# octanis_eps_v2.net
KiCad netlist of a schematic drawn in EAGLE
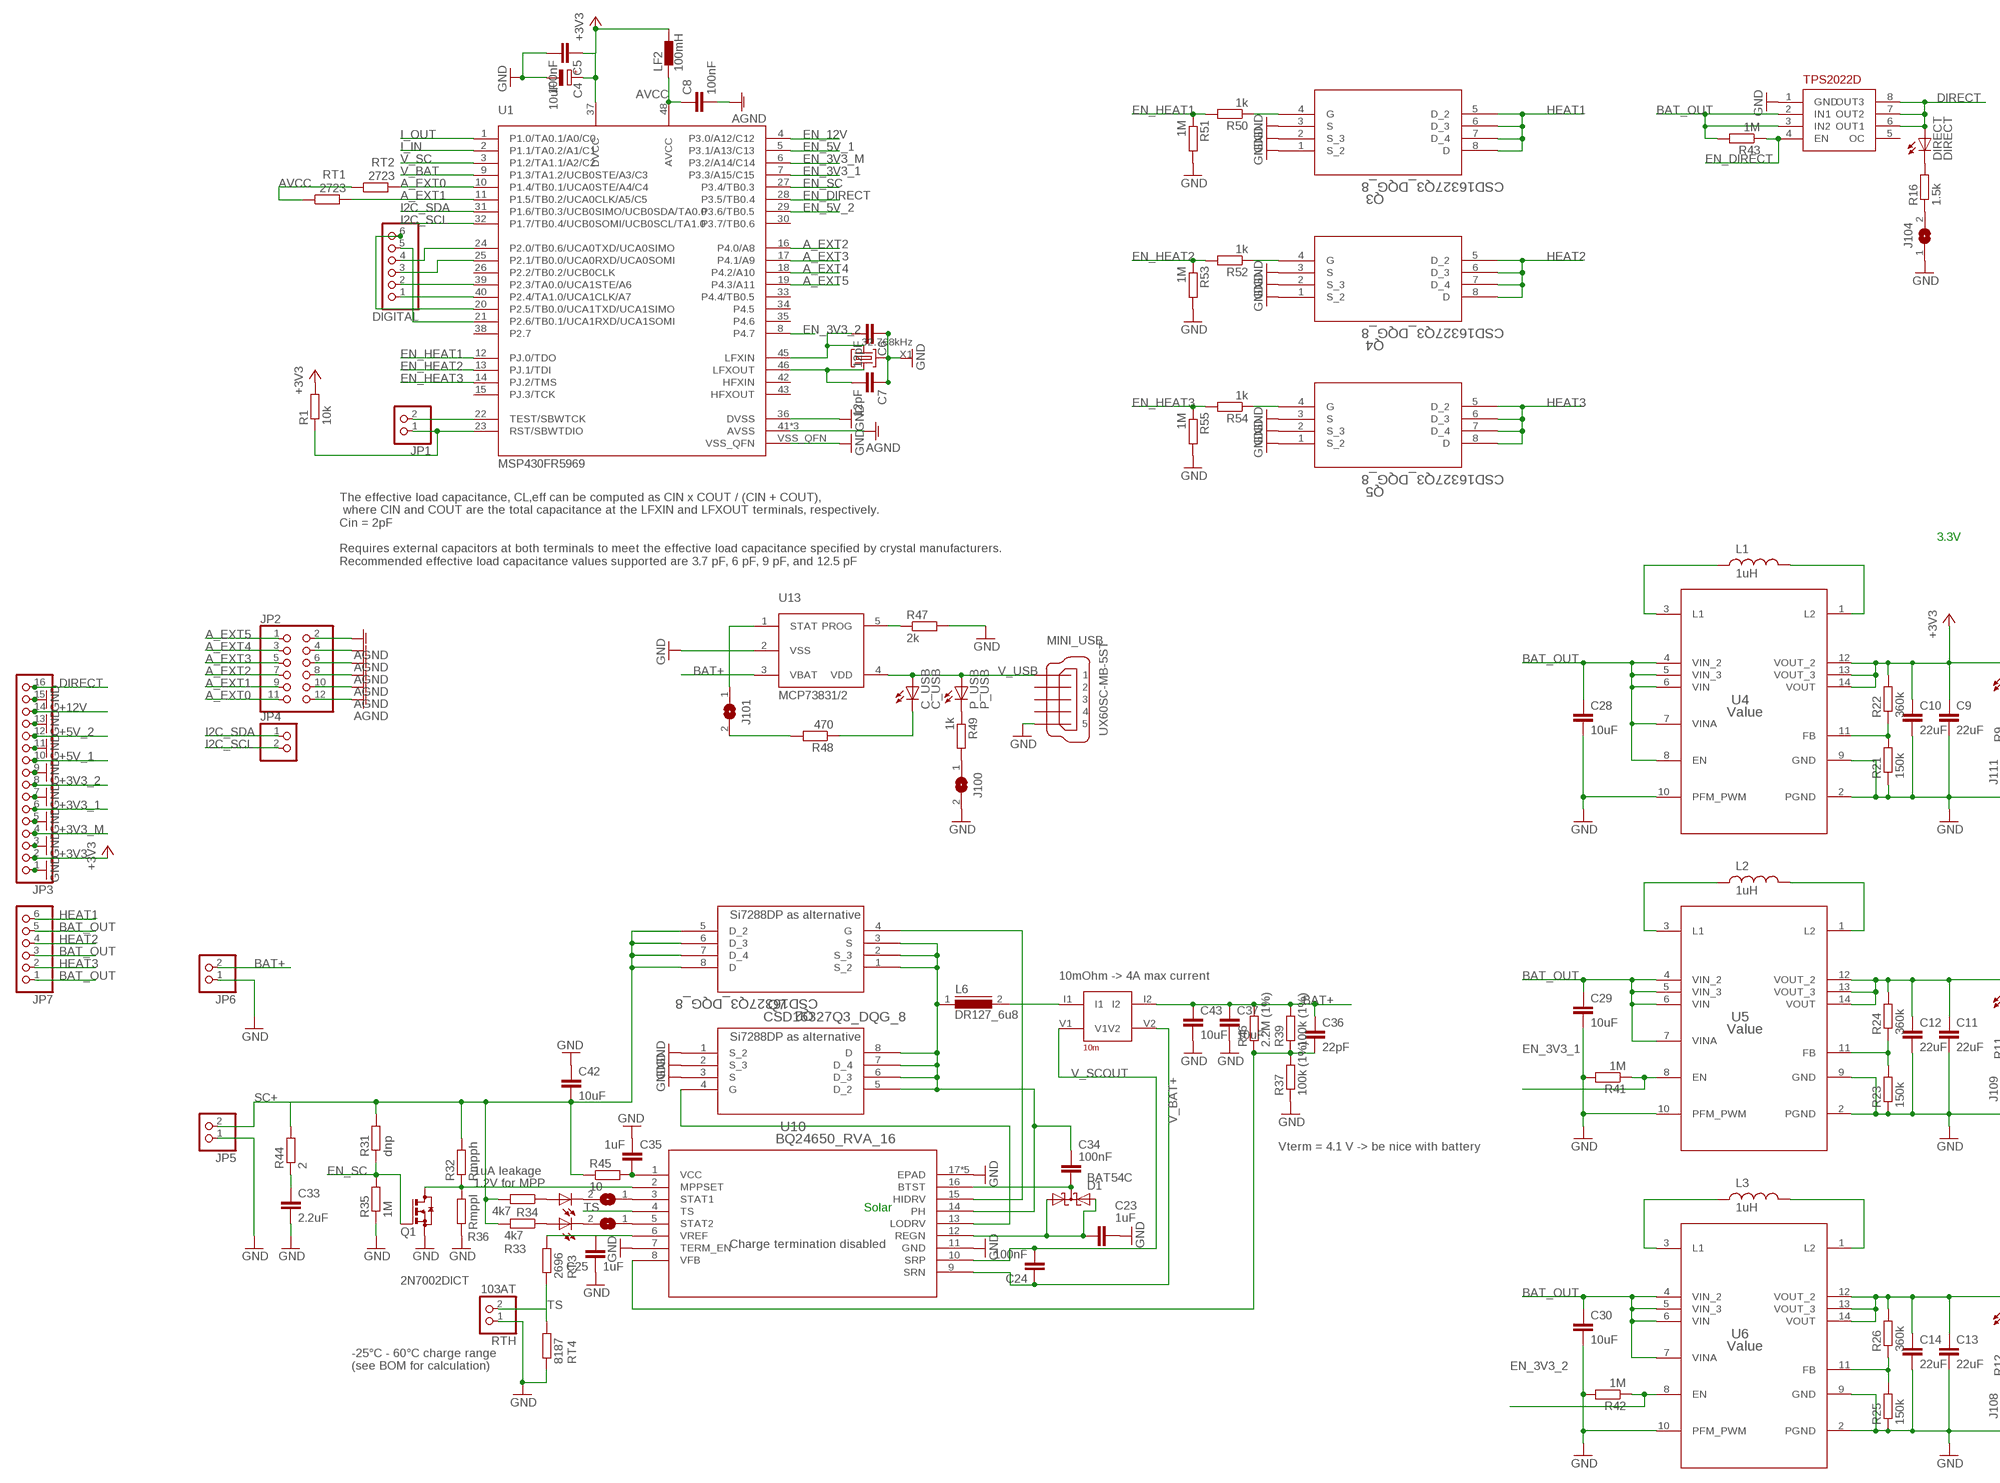
[diagram p0: schematic, sheet 1, part 1 of 2]
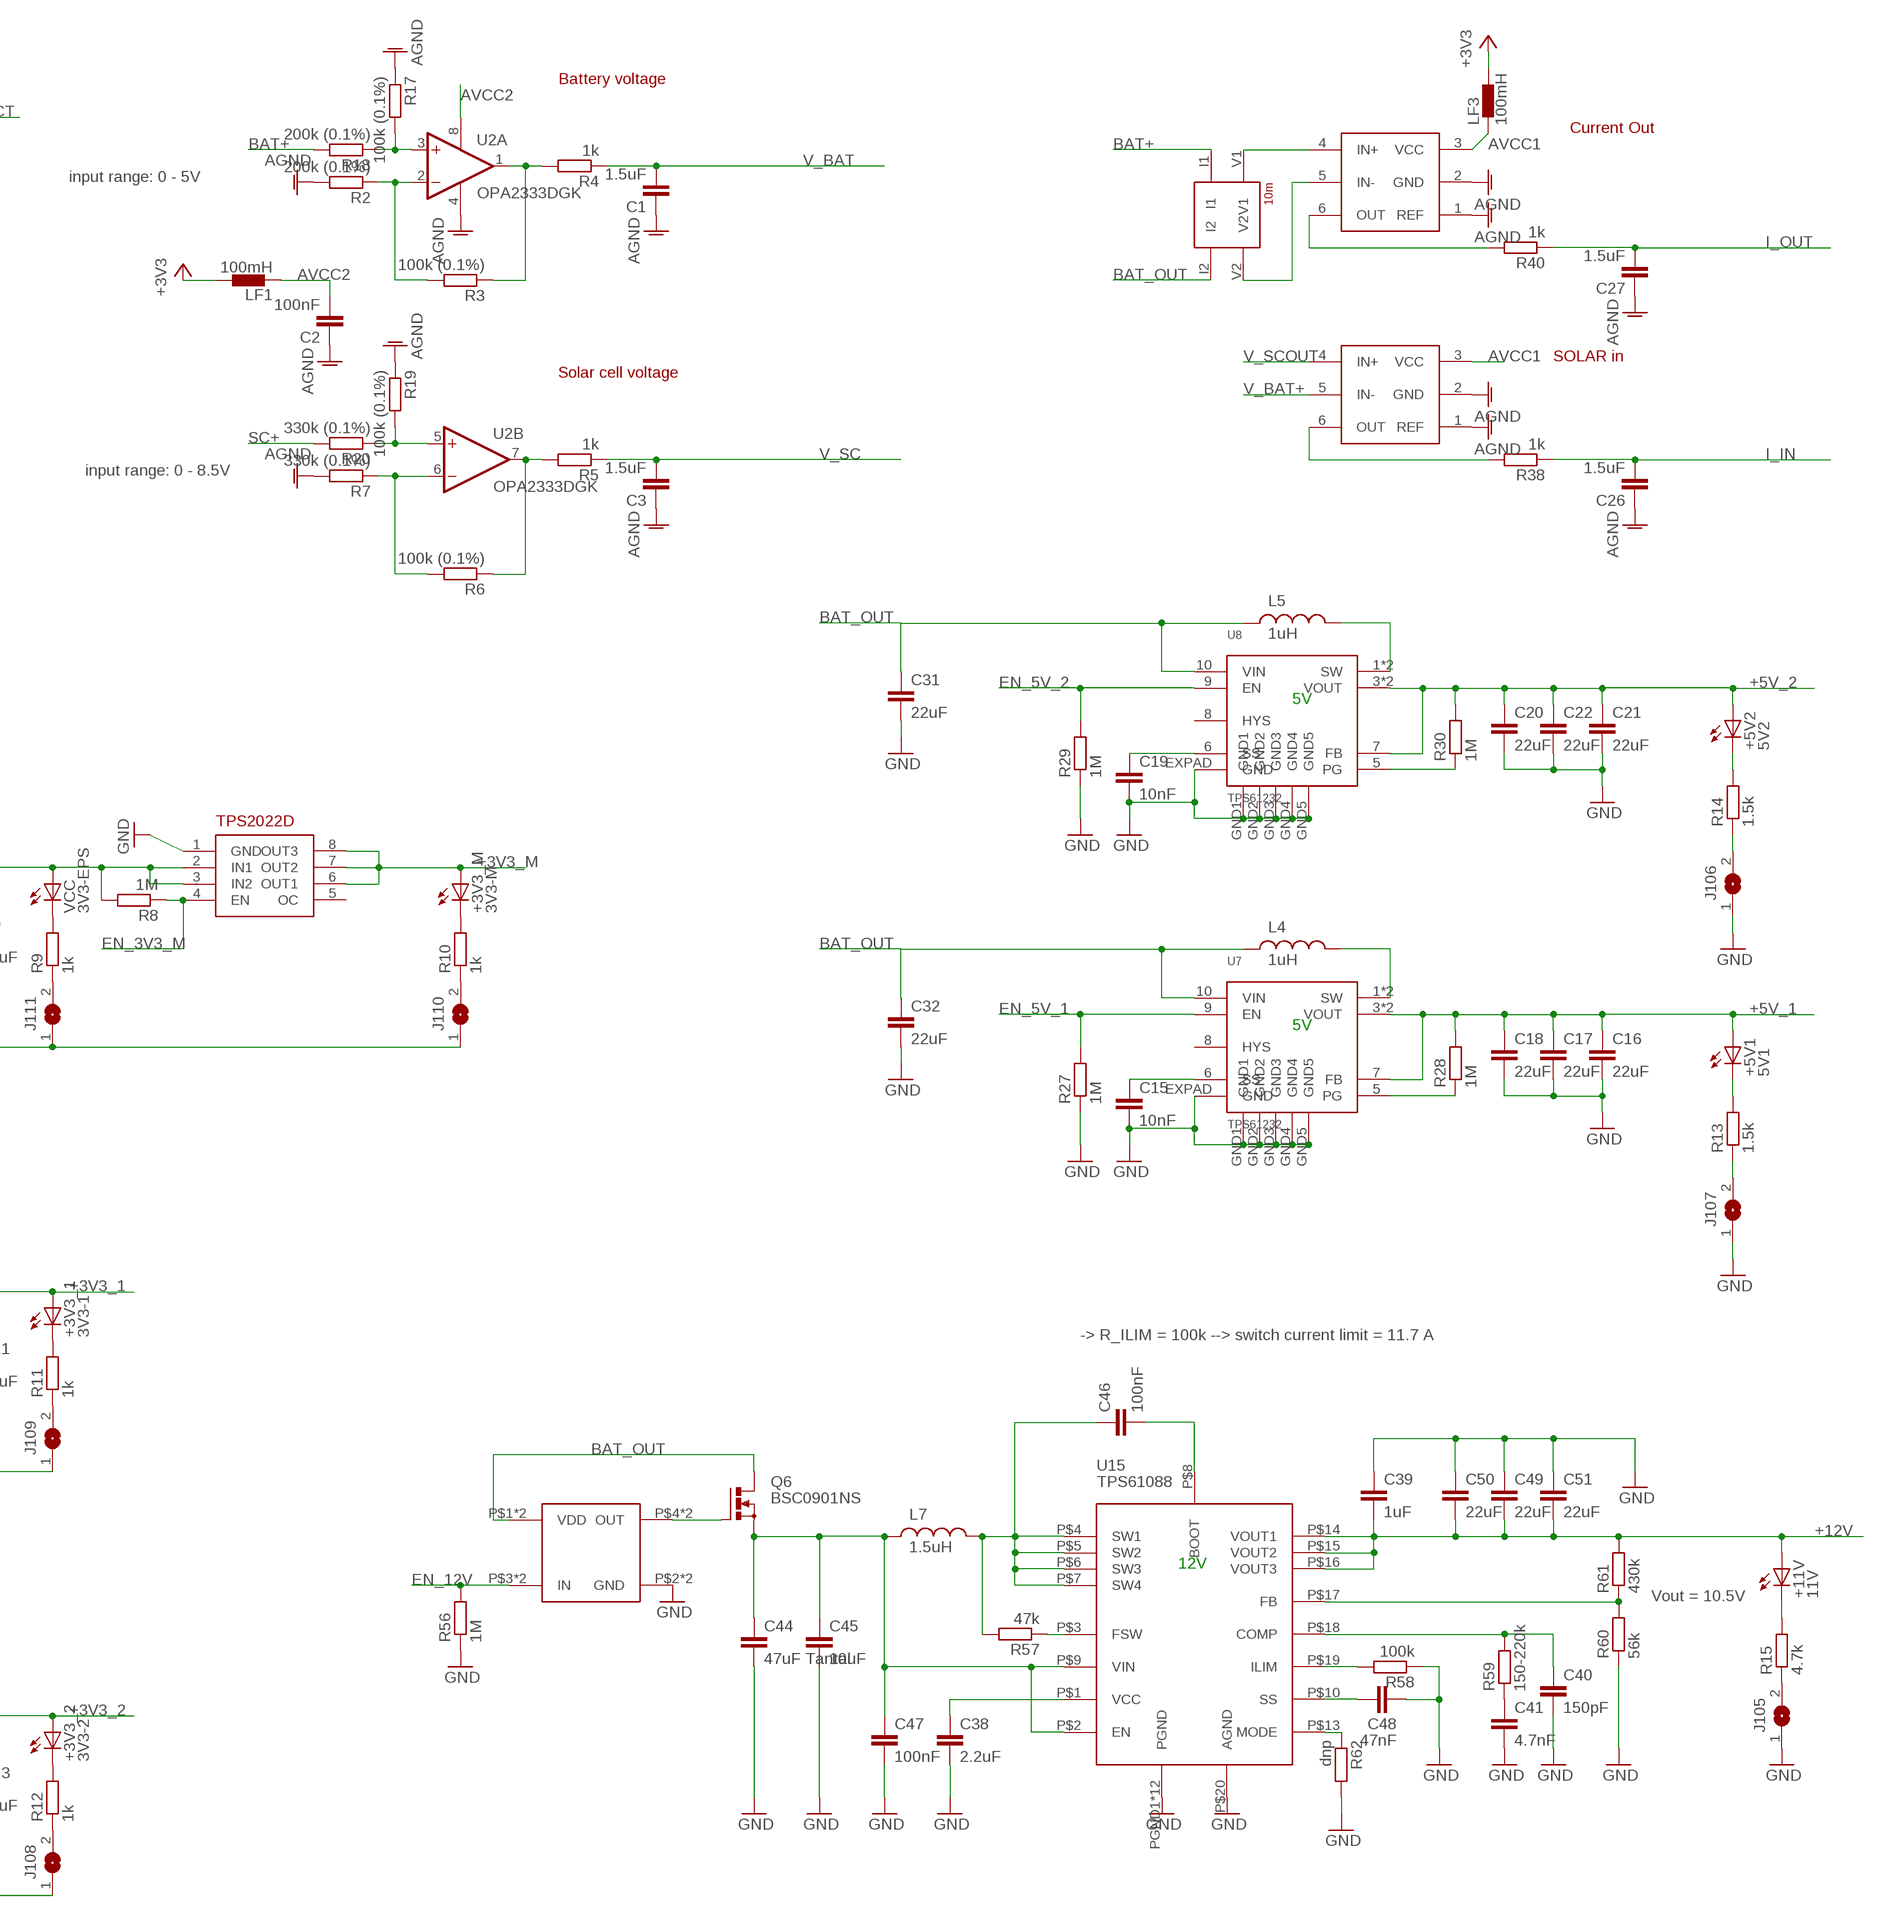
[diagram p1: schematic, sheet 1, part 2 of 2]

(export (version "E")
  (design (tool "Eeschema 10.0.6"))
  (components
    (comp (ref "+3V3_1")
      (value "3V3-1")
      (footprint "eagle-import:CHIPLED_0603")
      (libsource (lib "eagle-import") (part "LEDCHIPLED_0603"))
    )
    (comp (ref "+3V3_2")
      (value "3V3-2")
      (footprint "eagle-import:CHIPLED_0603")
      (libsource (lib "eagle-import") (part "LEDCHIPLED_0603"))
    )
    (comp (ref "+3V3_M")
      (value "3V3-M")
      (footprint "eagle-import:CHIPLED_0603")
      (libsource (lib "eagle-import") (part "LEDCHIPLED_0603"))
    )
    (comp (ref "+5V1")
      (value "5V1")
      (footprint "eagle-import:CHIPLED_0603")
      (libsource (lib "eagle-import") (part "LEDCHIPLED_0603"))
    )
    (comp (ref "+5V2")
      (value "5V2")
      (footprint "eagle-import:CHIPLED_0603")
      (libsource (lib "eagle-import") (part "LEDCHIPLED_0603"))
    )
    (comp (ref "+11V")
      (value "11V")
      (footprint "eagle-import:CHIPLED_0603")
      (libsource (lib "eagle-import") (part "LEDCHIPLED_0603"))
    )
    (comp (ref "C1")
      (value "1.5uF")
      (footprint "eagle-import:C0603")
      (libsource (lib "eagle-import") (part "C-EUC0603"))
    )
    (comp (ref "C2")
      (value "100nF")
      (footprint "eagle-import:C0603")
      (libsource (lib "eagle-import") (part "C-EUC0603"))
    )
    (comp (ref "C3")
      (value "1.5uF")
      (footprint "eagle-import:C0603")
      (libsource (lib "eagle-import") (part "C-EUC0603"))
    )
    (comp (ref "C4")
      (value "10uF")
      (footprint "eagle-import:A_3216-18R")
      (libsource (lib "eagle-import") (part "CPOL-EUA/3216-18R"))
    )
    (comp (ref "C5")
      (value "100nF")
      (footprint "eagle-import:C0603")
      (libsource (lib "eagle-import") (part "C-EUC0603"))
    )
    (comp (ref "C6")
      (value "12pF")
      (footprint "eagle-import:C0603")
      (libsource (lib "eagle-import") (part "C-EUC0603"))
    )
    (comp (ref "C7")
      (value "12pF")
      (footprint "eagle-import:C0603")
      (libsource (lib "eagle-import") (part "C-EUC0603"))
    )
    (comp (ref "C8")
      (value "100nF")
      (footprint "eagle-import:C0603")
      (libsource (lib "eagle-import") (part "C-EUC0603"))
    )
    (comp (ref "C9")
      (value "22uF")
      (footprint "eagle-import:C0805")
      (libsource (lib "eagle-import") (part "resistor_C-EUC0805"))
    )
    (comp (ref "C10")
      (value "22uF")
      (footprint "eagle-import:C0805")
      (libsource (lib "eagle-import") (part "resistor_C-EUC0805"))
    )
    (comp (ref "C11")
      (value "22uF")
      (footprint "eagle-import:C0805")
      (libsource (lib "eagle-import") (part "resistor_C-EUC0805"))
    )
    (comp (ref "C12")
      (value "22uF")
      (footprint "eagle-import:C0805")
      (libsource (lib "eagle-import") (part "resistor_C-EUC0805"))
    )
    (comp (ref "C13")
      (value "22uF")
      (footprint "eagle-import:C0805")
      (libsource (lib "eagle-import") (part "resistor_C-EUC0805"))
    )
    (comp (ref "C14")
      (value "22uF")
      (footprint "eagle-import:C0805")
      (libsource (lib "eagle-import") (part "resistor_C-EUC0805"))
    )
    (comp (ref "C15")
      (value "10nF")
      (footprint "eagle-import:C0603")
      (libsource (lib "eagle-import") (part "C-EUC0603"))
    )
    (comp (ref "C16")
      (value "22uF")
      (footprint "eagle-import:C0805")
      (libsource (lib "eagle-import") (part "resistor_C-EUC0805"))
    )
    (comp (ref "C17")
      (value "22uF")
      (footprint "eagle-import:C0805")
      (libsource (lib "eagle-import") (part "resistor_C-EUC0805"))
    )
    (comp (ref "C18")
      (value "22uF")
      (footprint "eagle-import:C0805")
      (libsource (lib "eagle-import") (part "resistor_C-EUC0805"))
    )
    (comp (ref "C19")
      (value "10nF")
      (footprint "eagle-import:C0603")
      (libsource (lib "eagle-import") (part "C-EUC0603"))
    )
    (comp (ref "C20")
      (value "22uF")
      (footprint "eagle-import:C0805")
      (libsource (lib "eagle-import") (part "resistor_C-EUC0805"))
    )
    (comp (ref "C21")
      (value "22uF")
      (footprint "eagle-import:C0805")
      (libsource (lib "eagle-import") (part "resistor_C-EUC0805"))
    )
    (comp (ref "C22")
      (value "22uF")
      (footprint "eagle-import:C0805")
      (libsource (lib "eagle-import") (part "resistor_C-EUC0805"))
    )
    (comp (ref "C23")
      (value "1uF")
      (footprint "eagle-import:C0603")
      (libsource (lib "eagle-import") (part "C-EUC0603"))
    )
    (comp (ref "C24")
      (value "100nF")
      (footprint "eagle-import:C0603")
      (libsource (lib "eagle-import") (part "C-EUC0603"))
    )
    (comp (ref "C25")
      (value "1uF")
      (footprint "eagle-import:C0603")
      (libsource (lib "eagle-import") (part "C-EUC0603"))
    )
    (comp (ref "C26")
      (value "1.5uF")
      (footprint "eagle-import:C0603")
      (libsource (lib "eagle-import") (part "C-EUC0603"))
    )
    (comp (ref "C27")
      (value "1.5uF")
      (footprint "eagle-import:C0603")
      (libsource (lib "eagle-import") (part "C-EUC0603"))
    )
    (comp (ref "C28")
      (value "10uF")
      (footprint "eagle-import:C0805")
      (libsource (lib "eagle-import") (part "resistor_C-EUC0805"))
    )
    (comp (ref "C29")
      (value "10uF")
      (footprint "eagle-import:C0805")
      (libsource (lib "eagle-import") (part "resistor_C-EUC0805"))
    )
    (comp (ref "C30")
      (value "10uF")
      (footprint "eagle-import:C0805")
      (libsource (lib "eagle-import") (part "resistor_C-EUC0805"))
    )
    (comp (ref "C31")
      (value "22uF")
      (footprint "eagle-import:C0805")
      (libsource (lib "eagle-import") (part "resistor_C-EUC0805"))
    )
    (comp (ref "C32")
      (value "22uF")
      (footprint "eagle-import:C0805")
      (libsource (lib "eagle-import") (part "resistor_C-EUC0805"))
    )
    (comp (ref "C33")
      (value "2.2uF")
      (footprint "eagle-import:C0603")
      (libsource (lib "eagle-import") (part "C-EUC0603"))
    )
    (comp (ref "C34")
      (value "100nF")
      (footprint "eagle-import:C0603")
      (libsource (lib "eagle-import") (part "C-EUC0603"))
    )
    (comp (ref "C35")
      (value "1uF")
      (footprint "eagle-import:C0603")
      (libsource (lib "eagle-import") (part "C-EUC0603"))
    )
    (comp (ref "C36")
      (value "22pF")
      (footprint "eagle-import:C0603")
      (libsource (lib "eagle-import") (part "C-EUC0603"))
    )
    (comp (ref "C37")
      (value "10uF")
      (footprint "eagle-import:C0805")
      (libsource (lib "eagle-import") (part "resistor_C-EUC0805"))
    )
    (comp (ref "C38")
      (value "2.2uF")
      (footprint "eagle-import:C0603")
      (libsource (lib "eagle-import") (part "C-EUC0603"))
    )
    (comp (ref "C39")
      (value "1uF")
      (footprint "eagle-import:C0603")
      (libsource (lib "eagle-import") (part "C-EUC0603"))
    )
    (comp (ref "C40")
      (value "150pF")
      (footprint "eagle-import:C0603")
      (libsource (lib "eagle-import") (part "C-EUC0603"))
    )
    (comp (ref "C41")
      (value "4.7nF")
      (footprint "eagle-import:C0603")
      (libsource (lib "eagle-import") (part "C-EUC0603"))
    )
    (comp (ref "C42")
      (value "10uF")
      (footprint "eagle-import:C0805")
      (libsource (lib "eagle-import") (part "resistor_C-EUC0805"))
    )
    (comp (ref "C43")
      (value "10uF")
      (footprint "eagle-import:C0805")
      (libsource (lib "eagle-import") (part "resistor_C-EUC0805"))
    )
    (comp (ref "C44")
      (value "47uF Tantal")
      (footprint "eagle-import:C1210")
      (libsource (lib "eagle-import") (part "C-EUC1210"))
    )
    (comp (ref "C45")
      (value "10uF")
      (footprint "eagle-import:C0805")
      (libsource (lib "eagle-import") (part "resistor_C-EUC0805"))
    )
    (comp (ref "C46")
      (value "100nF")
      (footprint "eagle-import:C0603")
      (libsource (lib "eagle-import") (part "C-EUC0603"))
    )
    (comp (ref "C47")
      (value "100nF")
      (footprint "eagle-import:C0603")
      (libsource (lib "eagle-import") (part "C-EUC0603"))
    )
    (comp (ref "C48")
      (value "47nF")
      (footprint "eagle-import:C0603")
      (libsource (lib "eagle-import") (part "C-EUC0603"))
    )
    (comp (ref "C49")
      (value "22uF")
      (footprint "eagle-import:C0805")
      (libsource (lib "eagle-import") (part "resistor_C-EUC0805"))
    )
    (comp (ref "C50")
      (value "22uF")
      (footprint "eagle-import:C0805")
      (libsource (lib "eagle-import") (part "resistor_C-EUC0805"))
    )
    (comp (ref "C51")
      (value "22uF")
      (footprint "eagle-import:C0805")
      (libsource (lib "eagle-import") (part "resistor_C-EUC0805"))
    )
    (comp (ref "C_USB")
      (value "C_USB")
      (footprint "eagle-import:CHIPLED_0603")
      (libsource (lib "eagle-import") (part "LEDCHIPLED_0603"))
    )
    (comp (ref "D1")
      (value "BAT54C")
      (footprint "eagle-import:SOT23")
      (libsource (lib "eagle-import") (part "BAT54C"))
    )
    (comp (ref "DIGITAL")
      (value "PINHD-1X6B")
      (footprint "eagle-import:1X06-BIG")
      (libsource (lib "eagle-import") (part "PINHD-1X6B"))
    )
    (comp (ref "DIRECT")
      (value "DIRECT")
      (footprint "eagle-import:CHIPLED_0603")
      (libsource (lib "eagle-import") (part "LEDCHIPLED_0603"))
    )
    (comp (ref "J100")
      (value "SJ")
      (footprint "eagle-import:SJ")
      (libsource (lib "eagle-import") (part "SJ"))
    )
    (comp (ref "J101")
      (value "SJ")
      (footprint "eagle-import:SJ")
      (libsource (lib "eagle-import") (part "SJ"))
    )
    (comp (ref "J102")
      (value "SJ")
      (footprint "eagle-import:SJ")
      (libsource (lib "eagle-import") (part "SJ"))
    )
    (comp (ref "J103")
      (value "SJ")
      (footprint "eagle-import:SJ")
      (libsource (lib "eagle-import") (part "SJ"))
    )
    (comp (ref "J104")
      (value "SJ")
      (footprint "eagle-import:SJ")
      (libsource (lib "eagle-import") (part "SJ"))
    )
    (comp (ref "J105")
      (value "SJ")
      (footprint "eagle-import:SJ")
      (libsource (lib "eagle-import") (part "SJ"))
    )
    (comp (ref "J106")
      (value "SJ")
      (footprint "eagle-import:SJ")
      (libsource (lib "eagle-import") (part "SJ"))
    )
    (comp (ref "J107")
      (value "SJ")
      (footprint "eagle-import:SJ")
      (libsource (lib "eagle-import") (part "SJ"))
    )
    (comp (ref "J108")
      (value "SJ")
      (footprint "eagle-import:SJ")
      (libsource (lib "eagle-import") (part "SJ"))
    )
    (comp (ref "J109")
      (value "SJ")
      (footprint "eagle-import:SJ")
      (libsource (lib "eagle-import") (part "SJ"))
    )
    (comp (ref "J110")
      (value "SJ")
      (footprint "eagle-import:SJ")
      (libsource (lib "eagle-import") (part "SJ"))
    )
    (comp (ref "J111")
      (value "SJ")
      (footprint "eagle-import:SJ")
      (libsource (lib "eagle-import") (part "SJ"))
    )
    (comp (ref "JP1")
      (value "PINHD-1X2")
      (footprint "eagle-import:1X02")
      (libsource (lib "eagle-import") (part "PINHD-1X2"))
    )
    (comp (ref "JP2")
      (value "PINHD-2X6")
      (footprint "eagle-import:2X06")
      (libsource (lib "eagle-import") (part "PINHD-2X6"))
    )
    (comp (ref "JP3")
      (value "PINHD-1X16")
      (footprint "eagle-import:1X16")
      (libsource (lib "eagle-import") (part "PINHD-1X16"))
    )
    (comp (ref "JP4")
      (value "PINHD-1X2")
      (footprint "eagle-import:1X02")
      (libsource (lib "eagle-import") (part "PINHD-1X2"))
    )
    (comp (ref "JP5")
      (value "PINHD-1X2")
      (footprint "eagle-import:1X02")
      (libsource (lib "eagle-import") (part "PINHD-1X2"))
    )
    (comp (ref "JP6")
      (value "PINHD-1X2")
      (footprint "eagle-import:1X02")
      (libsource (lib "eagle-import") (part "PINHD-1X2"))
    )
    (comp (ref "JP7")
      (value "PINHD-1X6")
      (footprint "eagle-import:1X06")
      (libsource (lib "eagle-import") (part "PINHD-1X6"))
    )
    (comp (ref "L1")
      (value "1uH")
      (footprint "eagle-import:XFL4020")
      (libsource (lib "eagle-import") (part "XFL4020"))
    )
    (comp (ref "L2")
      (value "1uH")
      (footprint "eagle-import:XFL4020")
      (libsource (lib "eagle-import") (part "XFL4020"))
    )
    (comp (ref "L3")
      (value "1uH")
      (footprint "eagle-import:XFL4020")
      (libsource (lib "eagle-import") (part "XFL4020"))
    )
    (comp (ref "L4")
      (value "1uH")
      (footprint "eagle-import:XFL4020")
      (libsource (lib "eagle-import") (part "XFL4020"))
    )
    (comp (ref "L5")
      (value "1uH")
      (footprint "eagle-import:XFL4020")
      (libsource (lib "eagle-import") (part "XFL4020"))
    )
    (comp (ref "L6")
      (value "DR127_6u8")
      (footprint "eagle-import:DR127")
      (libsource (lib "eagle-import") (part "DR127"))
    )
    (comp (ref "L7")
      (value "1.5uH")
      (footprint "eagle-import:XFL4020")
      (libsource (lib "eagle-import") (part "XFL4020"))
    )
    (comp (ref "LF1")
      (value "100mH")
      (footprint "eagle-import:0402")
      (libsource (lib "eagle-import") (part "BLM15HD601SN1"))
    )
    (comp (ref "LF2")
      (value "100mH")
      (footprint "eagle-import:0402")
      (libsource (lib "eagle-import") (part "BLM15HD601SN1"))
    )
    (comp (ref "LF3")
      (value "100mH")
      (footprint "eagle-import:0402")
      (libsource (lib "eagle-import") (part "BLM15HD601SN1"))
    )
    (comp (ref "MINI_USB")
      (value "UX60SC-MB-5ST")
      (footprint "eagle-import:UX60SC-MB-5ST")
      (libsource (lib "eagle-import") (part "UX60SC-MB-5ST"))
    )
    (comp (ref "P_USB")
      (value "P_USB")
      (footprint "eagle-import:CHIPLED_0603")
      (libsource (lib "eagle-import") (part "LEDCHIPLED_0603"))
    )
    (comp (ref "Q1")
      (value "BSS123")
      (footprint "eagle-import:SOT23")
      (libsource (lib "eagle-import") (part "BSS123"))
    )
    (comp (ref "Q2")
      (value "CSD16327Q3_DQG_8")
      (footprint "eagle-import:DQG8")
      (fields
        (field (name "GENERIC_PART_NUMBER") "CSD16327Q3")
        (field (name "MANUFACTURER") "Texas Instruments")
      )
      (libsource (lib "eagle-import") (part "CSD16327Q3_DQG_8"))
    )
    (comp (ref "Q3")
      (value "CSD16327Q3_DQG_8")
      (footprint "eagle-import:DQG8")
      (fields
        (field (name "GENERIC_PART_NUMBER") "CSD16327Q3")
        (field (name "MANUFACTURER") "Texas Instruments")
      )
      (libsource (lib "eagle-import") (part "CSD16327Q3_DQG_8"))
    )
    (comp (ref "Q4")
      (value "CSD16327Q3_DQG_8")
      (footprint "eagle-import:DQG8")
      (fields
        (field (name "GENERIC_PART_NUMBER") "CSD16327Q3")
        (field (name "MANUFACTURER") "Texas Instruments")
      )
      (libsource (lib "eagle-import") (part "CSD16327Q3_DQG_8"))
    )
    (comp (ref "Q5")
      (value "CSD16327Q3_DQG_8")
      (footprint "eagle-import:DQG8")
      (fields
        (field (name "GENERIC_PART_NUMBER") "CSD16327Q3")
        (field (name "MANUFACTURER") "Texas Instruments")
      )
      (libsource (lib "eagle-import") (part "CSD16327Q3_DQG_8"))
    )
    (comp (ref "Q6")
      (value "BSC0901NS")
      (footprint "eagle-import:PG-TDSON-8")
      (libsource (lib "eagle-import") (part "BSC340N08NS3G"))
    )
    (comp (ref "Q7")
      (value "CSD16327Q3_DQG_8")
      (footprint "eagle-import:DQG8")
      (fields
        (field (name "GENERIC_PART_NUMBER") "CSD16327Q3")
        (field (name "MANUFACTURER") "Texas Instruments")
      )
      (libsource (lib "eagle-import") (part "CSD16327Q3_DQG_8"))
    )
    (comp (ref "R1")
      (value "10k")
      (footprint "eagle-import:R0603")
      (libsource (lib "eagle-import") (part "R-EU_R0603"))
    )
    (comp (ref "R2")
      (value "200k (0.1%)")
      (footprint "eagle-import:R0603")
      (libsource (lib "eagle-import") (part "R-EU_R0603"))
    )
    (comp (ref "R3")
      (value "100k (0.1%)")
      (footprint "eagle-import:R0603")
      (libsource (lib "eagle-import") (part "R-EU_R0603"))
    )
    (comp (ref "R4")
      (value "1k")
      (footprint "eagle-import:R0603")
      (libsource (lib "eagle-import") (part "R-EU_R0603"))
    )
    (comp (ref "R5")
      (value "1k")
      (footprint "eagle-import:R0603")
      (libsource (lib "eagle-import") (part "R-EU_R0603"))
    )
    (comp (ref "R6")
      (value "100k (0.1%)")
      (footprint "eagle-import:R0603")
      (libsource (lib "eagle-import") (part "R-EU_R0603"))
    )
    (comp (ref "R7")
      (value "330k (0.1%)")
      (footprint "eagle-import:R0603")
      (libsource (lib "eagle-import") (part "R-EU_R0603"))
    )
    (comp (ref "R8")
      (value "1M")
      (footprint "eagle-import:R0603")
      (libsource (lib "eagle-import") (part "resistor_R-EU_R0603"))
    )
    (comp (ref "R9")
      (value "1k")
      (footprint "eagle-import:R0603")
      (libsource (lib "eagle-import") (part "R-EU_R0603"))
    )
    (comp (ref "R10")
      (value "1k")
      (footprint "eagle-import:R0603")
      (libsource (lib "eagle-import") (part "R-EU_R0603"))
    )
    (comp (ref "R11")
      (value "1k")
      (footprint "eagle-import:R0603")
      (libsource (lib "eagle-import") (part "R-EU_R0603"))
    )
    (comp (ref "R12")
      (value "1k")
      (footprint "eagle-import:R0603")
      (libsource (lib "eagle-import") (part "R-EU_R0603"))
    )
    (comp (ref "R13")
      (value "1.5k")
      (footprint "eagle-import:R0603")
      (libsource (lib "eagle-import") (part "R-EU_R0603"))
    )
    (comp (ref "R14")
      (value "1.5k")
      (footprint "eagle-import:R0603")
      (libsource (lib "eagle-import") (part "R-EU_R0603"))
    )
    (comp (ref "R15")
      (value "4.7k")
      (footprint "eagle-import:R0603")
      (libsource (lib "eagle-import") (part "R-EU_R0603"))
    )
    (comp (ref "R16")
      (value "1.5k")
      (footprint "eagle-import:R0603")
      (libsource (lib "eagle-import") (part "R-EU_R0603"))
    )
    (comp (ref "R17")
      (value "100k (0.1%)")
      (footprint "eagle-import:R0603")
      (libsource (lib "eagle-import") (part "R-EU_R0603"))
    )
    (comp (ref "R18")
      (value "200k (0.1%)")
      (footprint "eagle-import:R0603")
      (libsource (lib "eagle-import") (part "R-EU_R0603"))
    )
    (comp (ref "R19")
      (value "100k (0.1%)")
      (footprint "eagle-import:R0603")
      (libsource (lib "eagle-import") (part "R-EU_R0603"))
    )
    (comp (ref "R20")
      (value "330k (0.1%)")
      (footprint "eagle-import:R0603")
      (libsource (lib "eagle-import") (part "R-EU_R0603"))
    )
    (comp (ref "R21")
      (value "150k")
      (footprint "eagle-import:R0603")
      (libsource (lib "eagle-import") (part "R-EU_R0603"))
    )
    (comp (ref "R22")
      (value "360k")
      (footprint "eagle-import:R0603")
      (libsource (lib "eagle-import") (part "R-EU_R0603"))
    )
    (comp (ref "R23")
      (value "150k")
      (footprint "eagle-import:R0603")
      (libsource (lib "eagle-import") (part "R-EU_R0603"))
    )
    (comp (ref "R24")
      (value "360k")
      (footprint "eagle-import:R0603")
      (libsource (lib "eagle-import") (part "R-EU_R0603"))
    )
    (comp (ref "R25")
      (value "150k")
      (footprint "eagle-import:R0603")
      (libsource (lib "eagle-import") (part "R-EU_R0603"))
    )
    (comp (ref "R26")
      (value "360k")
      (footprint "eagle-import:R0603")
      (libsource (lib "eagle-import") (part "R-EU_R0603"))
    )
    (comp (ref "R27")
      (value "1M")
      (footprint "eagle-import:R0603")
      (libsource (lib "eagle-import") (part "R-EU_R0603"))
    )
    (comp (ref "R28")
      (value "1M")
      (footprint "eagle-import:R0603")
      (libsource (lib "eagle-import") (part "R-EU_R0603"))
    )
    (comp (ref "R29")
      (value "1M")
      (footprint "eagle-import:R0603")
      (libsource (lib "eagle-import") (part "R-EU_R0603"))
    )
    (comp (ref "R30")
      (value "1M")
      (footprint "eagle-import:R0603")
      (libsource (lib "eagle-import") (part "R-EU_R0603"))
    )
    (comp (ref "R31")
      (value "dnp")
      (footprint "eagle-import:R0603")
      (libsource (lib "eagle-import") (part "R-EU_R0603"))
    )
    (comp (ref "R32")
      (value "Rmpph")
      (footprint "eagle-import:R0603")
      (libsource (lib "eagle-import") (part "R-EU_R0603"))
    )
    (comp (ref "R33")
      (value "4k7")
      (footprint "eagle-import:R0603")
      (libsource (lib "eagle-import") (part "R-EU_R0603"))
    )
    (comp (ref "R34")
      (value "4k7")
      (footprint "eagle-import:R0603")
      (libsource (lib "eagle-import") (part "R-EU_R0603"))
    )
    (comp (ref "R35")
      (value "1M")
      (footprint "eagle-import:R0603")
      (libsource (lib "eagle-import") (part "R-EU_R0603"))
    )
    (comp (ref "R36")
      (value "Rmppl")
      (footprint "eagle-import:R0603")
      (libsource (lib "eagle-import") (part "R-EU_R0603"))
    )
    (comp (ref "R37")
      (value "100k (1%)")
      (footprint "eagle-import:R0603")
      (libsource (lib "eagle-import") (part "R-EU_R0603"))
    )
    (comp (ref "R38")
      (value "1k")
      (footprint "eagle-import:R0603")
      (libsource (lib "eagle-import") (part "R-EU_R0603"))
    )
    (comp (ref "R39")
      (value "100k (1%)")
      (footprint "eagle-import:R0603")
      (libsource (lib "eagle-import") (part "R-EU_R0603"))
    )
    (comp (ref "R40")
      (value "1k")
      (footprint "eagle-import:R0603")
      (libsource (lib "eagle-import") (part "R-EU_R0603"))
    )
    (comp (ref "R41")
      (value "1M")
      (footprint "eagle-import:R0603")
      (libsource (lib "eagle-import") (part "resistor_R-EU_R0603"))
    )
    (comp (ref "R42")
      (value "1M")
      (footprint "eagle-import:R0603")
      (libsource (lib "eagle-import") (part "resistor_R-EU_R0603"))
    )
    (comp (ref "R43")
      (value "1M")
      (footprint "eagle-import:R0603")
      (libsource (lib "eagle-import") (part "resistor_R-EU_R0603"))
    )
    (comp (ref "R44")
      (value "2")
      (footprint "eagle-import:R2010")
      (libsource (lib "eagle-import") (part "R-EU_R2010"))
    )
    (comp (ref "R45")
      (value "10")
      (footprint "eagle-import:R1206")
      (libsource (lib "eagle-import") (part "R-EU_R1206"))
    )
    (comp (ref "R46")
      (value "2.2M (1%)")
      (footprint "eagle-import:R0603")
      (libsource (lib "eagle-import") (part "R-EU_R0603"))
    )
    (comp (ref "R47")
      (value "2k")
      (footprint "eagle-import:R0603")
      (libsource (lib "eagle-import") (part "R-EU_R0603"))
    )
    (comp (ref "R48")
      (value "470")
      (footprint "eagle-import:R0603")
      (libsource (lib "eagle-import") (part "R-EU_R0603"))
    )
    (comp (ref "R49")
      (value "1k")
      (footprint "eagle-import:R0603")
      (libsource (lib "eagle-import") (part "R-EU_R0603"))
    )
    (comp (ref "R50")
      (value "1k")
      (footprint "eagle-import:R0603")
      (libsource (lib "eagle-import") (part "R-EU_R0603"))
    )
    (comp (ref "R51")
      (value "1M")
      (footprint "eagle-import:R0603")
      (libsource (lib "eagle-import") (part "R-EU_R0603"))
    )
    (comp (ref "R52")
      (value "1k")
      (footprint "eagle-import:R0603")
      (libsource (lib "eagle-import") (part "R-EU_R0603"))
    )
    (comp (ref "R53")
      (value "1M")
      (footprint "eagle-import:R0603")
      (libsource (lib "eagle-import") (part "R-EU_R0603"))
    )
    (comp (ref "R54")
      (value "1k")
      (footprint "eagle-import:R0603")
      (libsource (lib "eagle-import") (part "R-EU_R0603"))
    )
    (comp (ref "R55")
      (value "1M")
      (footprint "eagle-import:R0603")
      (libsource (lib "eagle-import") (part "R-EU_R0603"))
    )
    (comp (ref "R56")
      (value "1M")
      (footprint "eagle-import:R0603")
      (libsource (lib "eagle-import") (part "R-EU_R0603"))
    )
    (comp (ref "R57")
      (value "47k")
      (footprint "eagle-import:R0603")
      (libsource (lib "eagle-import") (part "resistor_R-EU_R0603"))
    )
    (comp (ref "R58")
      (value "100k")
      (footprint "eagle-import:R0603")
      (libsource (lib "eagle-import") (part "resistor_R-EU_R0603"))
    )
    (comp (ref "R59")
      (value "150-220k")
      (footprint "eagle-import:R0603")
      (libsource (lib "eagle-import") (part "resistor_R-EU_R0603"))
    )
    (comp (ref "R60")
      (value "56k")
      (footprint "eagle-import:R0603")
      (libsource (lib "eagle-import") (part "resistor_R-EU_R0603"))
    )
    (comp (ref "R61")
      (value "430k")
      (footprint "eagle-import:R0603")
      (libsource (lib "eagle-import") (part "resistor_R-EU_R0603"))
    )
    (comp (ref "R62")
      (value "dnp")
      (footprint "eagle-import:R0603")
      (libsource (lib "eagle-import") (part "resistor_R-EU_R0603"))
    )
    (comp (ref "RS1")
      (value "10m")
      (footprint "eagle-import:4PADS_RESISTOR")
      (libsource (lib "eagle-import") (part "CURRENT_RESISTOR"))
    )
    (comp (ref "RS2")
      (value "10m")
      (footprint "eagle-import:4PADS_RESISTOR")
      (libsource (lib "eagle-import") (part "CURRENT_RESISTOR"))
    )
    (comp (ref "RT1")
      (value "2723")
      (footprint "eagle-import:R0603")
      (libsource (lib "eagle-import") (part "R-EU_R0603"))
    )
    (comp (ref "RT2")
      (value "2723")
      (footprint "eagle-import:R0603")
      (libsource (lib "eagle-import") (part "R-EU_R0603"))
    )
    (comp (ref "RT3")
      (value "2696")
      (footprint "eagle-import:R0603")
      (libsource (lib "eagle-import") (part "R-EU_R0603"))
    )
    (comp (ref "RT4")
      (value "8187")
      (footprint "eagle-import:R0603")
      (libsource (lib "eagle-import") (part "R-EU_R0603"))
    )
    (comp (ref "RTH")
      (value "103AT")
      (footprint "eagle-import:1X02")
      (libsource (lib "eagle-import") (part "PINHD-1X2"))
    )
    (comp (ref "STAT1")
      (value "5V-ok")
      (footprint "eagle-import:CHIPLED_0603")
      (libsource (lib "eagle-import") (part "LEDCHIPLED_0603"))
    )
    (comp (ref "STAT2")
      (value "5V-ok")
      (footprint "eagle-import:CHIPLED_0603")
      (libsource (lib "eagle-import") (part "LEDCHIPLED_0603"))
    )
    (comp (ref "U1")
      (value "MSP430FR5969")
      (footprint "eagle-import:S-PVQFN-N48")
      (libsource (lib "eagle-import") (part "MSP430FR5969"))
    )
    (comp (ref "U2")
      (value "OPA2333DGK")
      (footprint "eagle-import:MSOP08")
      (libsource (lib "eagle-import") (part "OPA2333DGK"))
    )
    (comp (ref "U3")
      (value "TPS2022D")
      (footprint "eagle-import:SO8")
      (libsource (lib "eagle-import") (part "TPS2022D"))
    )
    (comp (ref "U4")
      (value "Value")
      (footprint "eagle-import:RNC0014A")
      (fields
        (field (name "ALTERNATEPARTNUMBER") "TPS630250RNCT")
        (field (name "MANUFACTURER") "Texas Instruments")
        (field (name "PARTNUMBER") "TPS630250RNCR")
      )
      (libsource (lib "eagle-import") (part "TPS630250RNCR"))
    )
    (comp (ref "U5")
      (value "Value")
      (footprint "eagle-import:RNC0014A")
      (fields
        (field (name "ALTERNATEPARTNUMBER") "TPS630250RNCT")
        (field (name "MANUFACTURER") "Texas Instruments")
        (field (name "PARTNUMBER") "TPS630250RNCR")
      )
      (libsource (lib "eagle-import") (part "TPS630250RNCR"))
    )
    (comp (ref "U6")
      (value "Value")
      (footprint "eagle-import:RNC0014A")
      (fields
        (field (name "ALTERNATEPARTNUMBER") "TPS630250RNCT")
        (field (name "MANUFACTURER") "Texas Instruments")
        (field (name "PARTNUMBER") "TPS630250RNCR")
      )
      (libsource (lib "eagle-import") (part "TPS630250RNCR"))
    )
    (comp (ref "U7")
      (value "TPS61232")
      (footprint "eagle-import:S-PVSON-N10")
      (libsource (lib "eagle-import") (part "TPS61232"))
    )
    (comp (ref "U8")
      (value "TPS61232")
      (footprint "eagle-import:S-PVSON-N10")
      (libsource (lib "eagle-import") (part "TPS61232"))
    )
    (comp (ref "U9")
      (value "TPS2022D")
      (footprint "eagle-import:SO8")
      (libsource (lib "eagle-import") (part "TPS2022D"))
    )
    (comp (ref "U10")
      (value "BQ24650_RVA_16")
      (footprint "eagle-import:RVA16_2P14X2P14")
      (fields
        (field (name "GENERIC_PART_NUMBER") "BQ24650")
        (field (name "MANUFACTURER") "Texas Instruments")
      )
      (libsource (lib "eagle-import") (part "BQ24650_RVA_16"))
    )
    (comp (ref "U11")
      (value "INA213")
      (footprint "eagle-import:SC70-6")
      (libsource (lib "eagle-import") (part "INA213"))
    )
    (comp (ref "U12")
      (value "INA213")
      (footprint "eagle-import:SC70-6")
      (libsource (lib "eagle-import") (part "INA213"))
    )
    (comp (ref "U13")
      (value "MCP73831/2")
      (footprint "eagle-import:SOT23-5")
      (libsource (lib "eagle-import") (part "MCP73831/2"))
    )
    (comp (ref "U14")
      (value "MIC5019")
      (footprint "eagle-import:QFN-4")
      (libsource (lib "eagle-import") (part "MIC5019"))
    )
    (comp (ref "U15")
      (value "TPS61088")
      (footprint "eagle-import:R-PVQFN-N20")
      (libsource (lib "eagle-import") (part "TPS61088"))
    )
    (comp (ref "VCC")
      (value "3V3-EPS")
      (footprint "eagle-import:CHIPLED_0603")
      (libsource (lib "eagle-import") (part "LEDCHIPLED_0603"))
    )
    (comp (ref "X1")
      (value "32.768kHz")
      (footprint "eagle-import:MS3V-T1R")
      (libsource (lib "eagle-import") (part "MS3V-T1R"))
    )
  )
  (nets
    (net (code "1") (name "+3V3") (class "Default")
      (node (ref "C10") (pin "1") (pinfunction "1_1") (pintype "passive"))
      (node (ref "C4") (pin "+") (pinfunction "+_+") (pintype "passive"))
      (node (ref "C5") (pin "1") (pinfunction "1_1") (pintype "passive"))
      (node (ref "C9") (pin "1") (pinfunction "1_1") (pintype "passive"))
      (node (ref "JP3") (pin "2") (pinfunction "2_2") (pintype "passive"))
      (node (ref "LF1") (pin "2") (pinfunction "2_2") (pintype "passive"))
      (node (ref "LF2") (pin "2") (pinfunction "2_2") (pintype "passive"))
      (node (ref "LF3") (pin "2") (pinfunction "2_2") (pintype "passive"))
      (node (ref "R1") (pin "2") (pinfunction "2_2") (pintype "passive"))
      (node (ref "R22") (pin "2") (pinfunction "2_2") (pintype "passive"))
      (node (ref "R8") (pin "2") (pinfunction "2_2") (pintype "passive"))
      (node (ref "U1") (pin "37") (pinfunction "DVCC_37") (pintype "bidirectional"))
      (node (ref "U3") (pin "2") (pinfunction "IN1_2") (pintype "bidirectional"))
      (node (ref "U3") (pin "3") (pinfunction "IN2_3") (pintype "bidirectional"))
      (node (ref "U4") (pin "12") (pinfunction "VOUT_2_12") (pintype "power_in"))
      (node (ref "U4") (pin "13") (pinfunction "VOUT_3_13") (pintype "power_in"))
      (node (ref "U4") (pin "14") (pinfunction "VOUT_14") (pintype "power_in"))
      (node (ref "VCC") (pin "A") (pinfunction "A_A") (pintype "passive"))
    )
    (net (code "2") (name "/+3V3_1") (class "Default")
      (node (ref "+3V3_1") (pin "A") (pinfunction "A_A") (pintype "passive"))
      (node (ref "C11") (pin "1") (pinfunction "1_1") (pintype "passive"))
      (node (ref "C12") (pin "1") (pinfunction "1_1") (pintype "passive"))
      (node (ref "JP3") (pin "6") (pinfunction "6_6") (pintype "passive"))
      (node (ref "R24") (pin "2") (pinfunction "2_2") (pintype "passive"))
      (node (ref "U5") (pin "12") (pinfunction "VOUT_2_12") (pintype "power_in"))
      (node (ref "U5") (pin "13") (pinfunction "VOUT_3_13") (pintype "power_in"))
      (node (ref "U5") (pin "14") (pinfunction "VOUT_14") (pintype "power_in"))
    )
    (net (code "3") (name "/+3V3_2") (class "Default")
      (node (ref "+3V3_2") (pin "A") (pinfunction "A_A") (pintype "passive"))
      (node (ref "C13") (pin "1") (pinfunction "1_1") (pintype "passive"))
      (node (ref "C14") (pin "1") (pinfunction "1_1") (pintype "passive"))
      (node (ref "JP3") (pin "8") (pinfunction "8_8") (pintype "passive"))
      (node (ref "R26") (pin "2") (pinfunction "2_2") (pintype "passive"))
      (node (ref "U6") (pin "12") (pinfunction "VOUT_2_12") (pintype "power_in"))
      (node (ref "U6") (pin "13") (pinfunction "VOUT_3_13") (pintype "power_in"))
      (node (ref "U6") (pin "14") (pinfunction "VOUT_14") (pintype "power_in"))
    )
    (net (code "4") (name "/+3V3_M") (class "Default")
      (node (ref "+3V3_M") (pin "A") (pinfunction "A_A") (pintype "passive"))
      (node (ref "JP3") (pin "4") (pinfunction "4_4") (pintype "passive"))
      (node (ref "U3") (pin "6") (pinfunction "OUT1_6") (pintype "bidirectional"))
      (node (ref "U3") (pin "7") (pinfunction "OUT2_7") (pintype "bidirectional"))
      (node (ref "U3") (pin "8") (pinfunction "OUT3_8") (pintype "bidirectional"))
    )
    (net (code "5") (name "/+5V_1") (class "Default")
      (node (ref "+5V1") (pin "A") (pinfunction "A_A") (pintype "passive"))
      (node (ref "C16") (pin "1") (pinfunction "1_1") (pintype "passive"))
      (node (ref "C17") (pin "1") (pinfunction "1_1") (pintype "passive"))
      (node (ref "C18") (pin "1") (pinfunction "1_1") (pintype "passive"))
      (node (ref "JP3") (pin "10") (pinfunction "10_10") (pintype "passive"))
      (node (ref "R28") (pin "2") (pinfunction "2_2") (pintype "passive"))
      (node (ref "U7") (pin "3") (pinfunction "VOUT_3") (pintype "power_in"))
      (node (ref "U7") (pin "4") (pinfunction "VOUT_4") (pintype "power_in"))
      (node (ref "U7") (pin "7") (pinfunction "FB_7") (pintype "input"))
    )
    (net (code "6") (name "/+5V_2") (class "Default")
      (node (ref "+5V2") (pin "A") (pinfunction "A_A") (pintype "passive"))
      (node (ref "C20") (pin "1") (pinfunction "1_1") (pintype "passive"))
      (node (ref "C21") (pin "1") (pinfunction "1_1") (pintype "passive"))
      (node (ref "C22") (pin "1") (pinfunction "1_1") (pintype "passive"))
      (node (ref "JP3") (pin "12") (pinfunction "12_12") (pintype "passive"))
      (node (ref "R30") (pin "2") (pinfunction "2_2") (pintype "passive"))
      (node (ref "U8") (pin "3") (pinfunction "VOUT_3") (pintype "power_in"))
      (node (ref "U8") (pin "4") (pinfunction "VOUT_4") (pintype "power_in"))
      (node (ref "U8") (pin "7") (pinfunction "FB_7") (pintype "input"))
    )
    (net (code "7") (name "/+12V") (class "Default")
      (node (ref "+11V") (pin "A") (pinfunction "A_A") (pintype "passive"))
      (node (ref "C39") (pin "2") (pinfunction "2_2") (pintype "passive"))
      (node (ref "C49") (pin "2") (pinfunction "2_2") (pintype "passive"))
      (node (ref "C50") (pin "2") (pinfunction "2_2") (pintype "passive"))
      (node (ref "C51") (pin "2") (pinfunction "2_2") (pintype "passive"))
      (node (ref "JP3") (pin "14") (pinfunction "14_14") (pintype "passive"))
      (node (ref "R61") (pin "2") (pinfunction "2_2") (pintype "passive"))
      (node (ref "U15") (pin "P$14") (pinfunction "VOUT1_P$14") (pintype "bidirectional"))
      (node (ref "U15") (pin "P$15") (pinfunction "VOUT2_P$15") (pintype "bidirectional"))
      (node (ref "U15") (pin "P$16") (pinfunction "VOUT3_P$16") (pintype "bidirectional"))
    )
    (net (code "8") (name "/AVCC") (class "Default")
      (node (ref "C8") (pin "1") (pinfunction "1_1") (pintype "passive"))
      (node (ref "LF2") (pin "1") (pinfunction "1_1") (pintype "passive"))
      (node (ref "RT1") (pin "1") (pinfunction "1_1") (pintype "passive"))
      (node (ref "RT2") (pin "1") (pinfunction "1_1") (pintype "passive"))
      (node (ref "U1") (pin "48") (pinfunction "AVCC_48") (pintype "bidirectional"))
    )
    (net (code "9") (name "/AVCC1") (class "Default")
      (node (ref "LF3") (pin "1") (pinfunction "1_1") (pintype "passive"))
      (node (ref "U11") (pin "3") (pinfunction "VCC_3") (pintype "bidirectional"))
      (node (ref "U12") (pin "3") (pinfunction "VCC_3") (pintype "bidirectional"))
    )
    (net (code "10") (name "/AVCC2") (class "Default")
      (node (ref "C2") (pin "2") (pinfunction "2_2") (pintype "passive"))
      (node (ref "LF1") (pin "1") (pinfunction "1_1") (pintype "passive"))
      (node (ref "U2") (pin "8") (pinfunction "V+_8") (pintype "power_in"))
    )
    (net (code "11") (name "/A_EXT0") (class "Default")
      (node (ref "JP2") (pin "11") (pinfunction "11_11") (pintype "passive"))
      (node (ref "RT2") (pin "2") (pinfunction "2_2") (pintype "passive"))
      (node (ref "U1") (pin "10") (pinfunction "P1.4/TB0.1/UCA0STE/A4/C4_10") (pintype "bidirectional"))
    )
    (net (code "12") (name "/A_EXT1") (class "Default")
      (node (ref "JP2") (pin "9") (pinfunction "9_9") (pintype "passive"))
      (node (ref "RT1") (pin "2") (pinfunction "2_2") (pintype "passive"))
      (node (ref "U1") (pin "11") (pinfunction "P1.5/TB0.2/UCA0CLK/A5/C5_11") (pintype "bidirectional"))
    )
    (net (code "13") (name "/A_EXT2") (class "Default")
      (node (ref "JP2") (pin "7") (pinfunction "7_7") (pintype "passive"))
      (node (ref "U1") (pin "16") (pinfunction "P4.0/A8_16") (pintype "bidirectional"))
    )
    (net (code "14") (name "/A_EXT3") (class "Default")
      (node (ref "JP2") (pin "5") (pinfunction "5_5") (pintype "passive"))
      (node (ref "U1") (pin "17") (pinfunction "P4.1/A9_17") (pintype "bidirectional"))
    )
    (net (code "15") (name "/A_EXT4") (class "Default")
      (node (ref "JP2") (pin "3") (pinfunction "3_3") (pintype "passive"))
      (node (ref "U1") (pin "18") (pinfunction "P4.2/A10_18") (pintype "bidirectional"))
    )
    (net (code "16") (name "/A_EXT5") (class "Default")
      (node (ref "JP2") (pin "1") (pinfunction "1_1") (pintype "passive"))
      (node (ref "U1") (pin "19") (pinfunction "P4.3/A11_19") (pintype "bidirectional"))
    )
    (net (code "17") (name "/BAT+") (class "Default")
      (node (ref "C36") (pin "1") (pinfunction "1_1") (pintype "passive"))
      (node (ref "C37") (pin "1") (pinfunction "1_1") (pintype "passive"))
      (node (ref "C43") (pin "1") (pinfunction "1_1") (pintype "passive"))
      (node (ref "JP6") (pin "2") (pinfunction "2_2") (pintype "passive"))
      (node (ref "R18") (pin "2") (pinfunction "2_2") (pintype "passive"))
      (node (ref "R39") (pin "2") (pinfunction "2_2") (pintype "passive"))
      (node (ref "R46") (pin "2") (pinfunction "2_2") (pintype "passive"))
      (node (ref "RS1") (pin "I1") (pinfunction "I1_I1") (pintype "bidirectional"))
      (node (ref "RS2") (pin "I2") (pinfunction "I2_I2") (pintype "bidirectional"))
      (node (ref "U13") (pin "3") (pinfunction "VBAT_3") (pintype "bidirectional"))
    )
    (net (code "18") (name "/BAT_OUT") (class "Default")
      (node (ref "C28") (pin "1") (pinfunction "1_1") (pintype "passive"))
      (node (ref "C29") (pin "1") (pinfunction "1_1") (pintype "passive"))
      (node (ref "C30") (pin "1") (pinfunction "1_1") (pintype "passive"))
      (node (ref "C31") (pin "1") (pinfunction "1_1") (pintype "passive"))
      (node (ref "C32") (pin "1") (pinfunction "1_1") (pintype "passive"))
      (node (ref "JP7") (pin "1") (pinfunction "1_1") (pintype "passive"))
      (node (ref "JP7") (pin "3") (pinfunction "3_3") (pintype "passive"))
      (node (ref "JP7") (pin "5") (pinfunction "5_5") (pintype "passive"))
      (node (ref "L4") (pin "P$1") (pinfunction "1_P$1") (pintype "passive"))
      (node (ref "L5") (pin "P$1") (pinfunction "1_P$1") (pintype "passive"))
      (node (ref "Q6") (pin "5") (pinfunction "D_5") (pintype "passive"))
      (node (ref "Q6") (pin "6") (pinfunction "D_6") (pintype "passive"))
      (node (ref "Q6") (pin "7") (pinfunction "D_7") (pintype "passive"))
      (node (ref "Q6") (pin "8") (pinfunction "D_8") (pintype "passive"))
      (node (ref "R43") (pin "2") (pinfunction "2_2") (pintype "passive"))
      (node (ref "RS1") (pin "I2") (pinfunction "I2_I2") (pintype "bidirectional"))
      (node (ref "U14") (pin "P$1") (pinfunction "VDD_P$1") (pintype "bidirectional"))
      (node (ref "U14") (pin "P1") (pinfunction "VDD_P1") (pintype "bidirectional"))
      (node (ref "U4") (pin "4") (pinfunction "VIN_2_4") (pintype "power_in"))
      (node (ref "U4") (pin "5") (pinfunction "VIN_3_5") (pintype "power_in"))
      (node (ref "U4") (pin "6") (pinfunction "VIN_6") (pintype "power_in"))
      (node (ref "U4") (pin "7") (pinfunction "VINA_7") (pintype "power_in"))
      (node (ref "U4") (pin "8") (pinfunction "EN_8") (pintype "input"))
      (node (ref "U5") (pin "4") (pinfunction "VIN_2_4") (pintype "power_in"))
      (node (ref "U5") (pin "5") (pinfunction "VIN_3_5") (pintype "power_in"))
      (node (ref "U5") (pin "6") (pinfunction "VIN_6") (pintype "power_in"))
      (node (ref "U5") (pin "7") (pinfunction "VINA_7") (pintype "power_in"))
      (node (ref "U6") (pin "4") (pinfunction "VIN_2_4") (pintype "power_in"))
      (node (ref "U6") (pin "5") (pinfunction "VIN_3_5") (pintype "power_in"))
      (node (ref "U6") (pin "6") (pinfunction "VIN_6") (pintype "power_in"))
      (node (ref "U6") (pin "7") (pinfunction "VINA_7") (pintype "power_in"))
      (node (ref "U7") (pin "10") (pinfunction "VIN_10") (pintype "input"))
      (node (ref "U8") (pin "10") (pinfunction "VIN_10") (pintype "input"))
      (node (ref "U9") (pin "2") (pinfunction "IN1_2") (pintype "bidirectional"))
      (node (ref "U9") (pin "3") (pinfunction "IN2_3") (pintype "bidirectional"))
    )
    (net (code "19") (name "/DIRECT") (class "Default")
      (node (ref "DIRECT") (pin "A") (pinfunction "A_A") (pintype "passive"))
      (node (ref "JP3") (pin "16") (pinfunction "16_16") (pintype "passive"))
      (node (ref "U9") (pin "6") (pinfunction "OUT1_6") (pintype "bidirectional"))
      (node (ref "U9") (pin "7") (pinfunction "OUT2_7") (pintype "bidirectional"))
      (node (ref "U9") (pin "8") (pinfunction "OUT3_8") (pintype "bidirectional"))
    )
    (net (code "20") (name "/EN_3V3_1") (class "Default")
      (node (ref "R41") (pin "1") (pinfunction "1_1") (pintype "passive"))
      (node (ref "U1") (pin "7") (pinfunction "P3.3/A15/C15_7") (pintype "bidirectional"))
      (node (ref "U5") (pin "8") (pinfunction "EN_8") (pintype "input"))
    )
    (net (code "21") (name "/EN_3V3_2") (class "Default")
      (node (ref "R42") (pin "1") (pinfunction "1_1") (pintype "passive"))
      (node (ref "U1") (pin "8") (pinfunction "P4.7_8") (pintype "bidirectional"))
      (node (ref "U6") (pin "8") (pinfunction "EN_8") (pintype "input"))
    )
    (net (code "22") (name "/EN_3V3_M") (class "Default")
      (node (ref "R8") (pin "1") (pinfunction "1_1") (pintype "passive"))
      (node (ref "U1") (pin "6") (pinfunction "P3.2/A14/C14_6") (pintype "bidirectional"))
      (node (ref "U3") (pin "4") (pinfunction "EN_4") (pintype "bidirectional"))
    )
    (net (code "23") (name "/EN_5V_1") (class "Default")
      (node (ref "R27") (pin "2") (pinfunction "2_2") (pintype "passive"))
      (node (ref "U1") (pin "5") (pinfunction "P3.1/A13/C13_5") (pintype "bidirectional"))
      (node (ref "U7") (pin "9") (pinfunction "EN_9") (pintype "input"))
    )
    (net (code "24") (name "/EN_5V_2") (class "Default")
      (node (ref "R29") (pin "2") (pinfunction "2_2") (pintype "passive"))
      (node (ref "U1") (pin "29") (pinfunction "P3.6/TB0.5_29") (pintype "bidirectional"))
      (node (ref "U8") (pin "9") (pinfunction "EN_9") (pintype "input"))
    )
    (net (code "25") (name "/EN_12V") (class "Default")
      (node (ref "R56") (pin "2") (pinfunction "2_2") (pintype "passive"))
      (node (ref "U1") (pin "4") (pinfunction "P3.0/A12/C12_4") (pintype "bidirectional"))
      (node (ref "U14") (pin "P$3") (pinfunction "IN_P$3") (pintype "bidirectional"))
      (node (ref "U14") (pin "P3") (pinfunction "IN_P3") (pintype "bidirectional"))
    )
    (net (code "26") (name "/EN_DIRECT") (class "Default")
      (node (ref "R43") (pin "1") (pinfunction "1_1") (pintype "passive"))
      (node (ref "U1") (pin "28") (pinfunction "P3.5/TB0.4_28") (pintype "bidirectional"))
      (node (ref "U9") (pin "4") (pinfunction "EN_4") (pintype "bidirectional"))
    )
    (net (code "27") (name "/EN_HEAT1") (class "Default")
      (node (ref "R50") (pin "2") (pinfunction "2_2") (pintype "passive"))
      (node (ref "R51") (pin "1") (pinfunction "1_1") (pintype "passive"))
      (node (ref "U1") (pin "12") (pinfunction "PJ.0/TDO_12") (pintype "bidirectional"))
    )
    (net (code "28") (name "/EN_HEAT2") (class "Default")
      (node (ref "R52") (pin "2") (pinfunction "2_2") (pintype "passive"))
      (node (ref "R53") (pin "1") (pinfunction "1_1") (pintype "passive"))
      (node (ref "U1") (pin "13") (pinfunction "PJ.1/TDI_13") (pintype "bidirectional"))
    )
    (net (code "29") (name "/EN_HEAT3") (class "Default")
      (node (ref "R54") (pin "2") (pinfunction "2_2") (pintype "passive"))
      (node (ref "R55") (pin "1") (pinfunction "1_1") (pintype "passive"))
      (node (ref "U1") (pin "14") (pinfunction "PJ.2/TMS_14") (pintype "bidirectional"))
    )
    (net (code "30") (name "/EN_SC") (class "Default")
      (node (ref "Q1") (pin "1") (pinfunction "G_1") (pintype "passive"))
      (node (ref "R31") (pin "1") (pinfunction "1_1") (pintype "passive"))
      (node (ref "R35") (pin "2") (pinfunction "2_2") (pintype "passive"))
      (node (ref "U1") (pin "27") (pinfunction "P3.4/TB0.3_27") (pintype "bidirectional"))
    )
    (net (code "31") (name "/HEAT1") (class "Default")
      (node (ref "JP7") (pin "6") (pinfunction "6_6") (pintype "passive"))
      (node (ref "Q3") (pin "5") (pinfunction "D_2_5") (pintype "passive"))
      (node (ref "Q3") (pin "6") (pinfunction "D_3_6") (pintype "passive"))
      (node (ref "Q3") (pin "7") (pinfunction "D_4_7") (pintype "passive"))
      (node (ref "Q3") (pin "8") (pinfunction "D_8") (pintype "passive"))
    )
    (net (code "32") (name "/HEAT2") (class "Default")
      (node (ref "JP7") (pin "4") (pinfunction "4_4") (pintype "passive"))
      (node (ref "Q4") (pin "5") (pinfunction "D_2_5") (pintype "passive"))
      (node (ref "Q4") (pin "6") (pinfunction "D_3_6") (pintype "passive"))
      (node (ref "Q4") (pin "7") (pinfunction "D_4_7") (pintype "passive"))
      (node (ref "Q4") (pin "8") (pinfunction "D_8") (pintype "passive"))
    )
    (net (code "33") (name "/HEAT3") (class "Default")
      (node (ref "JP7") (pin "2") (pinfunction "2_2") (pintype "passive"))
      (node (ref "Q5") (pin "5") (pinfunction "D_2_5") (pintype "passive"))
      (node (ref "Q5") (pin "6") (pinfunction "D_3_6") (pintype "passive"))
      (node (ref "Q5") (pin "7") (pinfunction "D_4_7") (pintype "passive"))
      (node (ref "Q5") (pin "8") (pinfunction "D_8") (pintype "passive"))
    )
    (net (code "34") (name "/I2C_SCL") (class "Default")
      (node (ref "JP4") (pin "2") (pinfunction "2_2") (pintype "passive"))
      (node (ref "U1") (pin "32") (pinfunction "P1.7/TB0.4/UCB0SOMI/UCB0SCL/TA1.0_32") (pintype "bidirectional"))
    )
    (net (code "35") (name "/I2C_SDA") (class "Default")
      (node (ref "JP4") (pin "1") (pinfunction "1_1") (pintype "passive"))
      (node (ref "U1") (pin "31") (pinfunction "P1.6/TB0.3/UCB0SIMO/UCB0SDA/TA0.0_31") (pintype "bidirectional"))
    )
    (net (code "36") (name "/I_IN") (class "Default")
      (node (ref "C26") (pin "2") (pinfunction "2_2") (pintype "passive"))
      (node (ref "R38") (pin "1") (pinfunction "1_1") (pintype "passive"))
      (node (ref "U1") (pin "2") (pinfunction "P1.1/TA0.2/A1/C1_2") (pintype "bidirectional"))
    )
    (net (code "37") (name "/I_OUT") (class "Default")
      (node (ref "C27") (pin "2") (pinfunction "2_2") (pintype "passive"))
      (node (ref "R40") (pin "1") (pinfunction "1_1") (pintype "passive"))
      (node (ref "U1") (pin "1") (pinfunction "P1.0/TA0.1/A0/C0_1") (pintype "bidirectional"))
    )
    (net (code "38") (name "/SC+") (class "Default")
      (node (ref "C42") (pin "2") (pinfunction "2_2") (pintype "passive"))
      (node (ref "JP5") (pin "2") (pinfunction "2_2") (pintype "passive"))
      (node (ref "Q2") (pin "5") (pinfunction "D_2_5") (pintype "passive"))
      (node (ref "Q2") (pin "6") (pinfunction "D_3_6") (pintype "passive"))
      (node (ref "Q2") (pin "7") (pinfunction "D_4_7") (pintype "passive"))
      (node (ref "Q2") (pin "8") (pinfunction "D_8") (pintype "passive"))
      (node (ref "R20") (pin "2") (pinfunction "2_2") (pintype "passive"))
      (node (ref "R31") (pin "2") (pinfunction "2_2") (pintype "passive"))
      (node (ref "R32") (pin "2") (pinfunction "2_2") (pintype "passive"))
      (node (ref "R33") (pin "2") (pinfunction "2_2") (pintype "passive"))
      (node (ref "R34") (pin "2") (pinfunction "2_2") (pintype "passive"))
      (node (ref "R44") (pin "2") (pinfunction "2_2") (pintype "passive"))
      (node (ref "R45") (pin "1") (pinfunction "1_1") (pintype "passive"))
    )
    (net (code "39") (name "/TS") (class "Default")
      (node (ref "RT3") (pin "2") (pinfunction "2_2") (pintype "passive"))
      (node (ref "RT4") (pin "1") (pinfunction "1_1") (pintype "passive"))
      (node (ref "RTH") (pin "2") (pinfunction "2_2") (pintype "passive"))
      (node (ref "U10") (pin "4") (pinfunction "TS_4") (pintype "input"))
    )
    (net (code "40") (name "/V_BAT") (class "Default")
      (node (ref "C1") (pin "2") (pinfunction "2_2") (pintype "passive"))
      (node (ref "R4") (pin "1") (pinfunction "1_1") (pintype "passive"))
      (node (ref "U1") (pin "9") (pinfunction "P1.3/TA1.2/UCB0STE/A3/C3_9") (pintype "bidirectional"))
    )
    (net (code "41") (name "/V_BAT+") (class "Default")
      (node (ref "C24") (pin "1") (pinfunction "1_1") (pintype "passive"))
      (node (ref "RS2") (pin "V2") (pinfunction "V2_V2") (pintype "bidirectional"))
      (node (ref "U10") (pin "9") (pinfunction "SRN_9") (pintype "input"))
      (node (ref "U12") (pin "5") (pinfunction "IN-_5") (pintype "bidirectional"))
    )
    (net (code "42") (name "/V_SC") (class "Default")
      (node (ref "C3") (pin "2") (pinfunction "2_2") (pintype "passive"))
      (node (ref "R5") (pin "1") (pinfunction "1_1") (pintype "passive"))
      (node (ref "U1") (pin "3") (pinfunction "P1.2/TA1.1/A2/C2_3") (pintype "bidirectional"))
    )
    (net (code "43") (name "/V_SCOUT") (class "Default")
      (node (ref "C24") (pin "2") (pinfunction "2_2") (pintype "passive"))
      (node (ref "RS2") (pin "V1") (pinfunction "V1_V1") (pintype "bidirectional"))
      (node (ref "U10") (pin "10") (pinfunction "SRP_10") (pintype "bidirectional"))
      (node (ref "U12") (pin "4") (pinfunction "IN+_4") (pintype "bidirectional"))
    )
    (net (code "44") (name "/V_USB") (class "Default")
      (node (ref "C_USB") (pin "A") (pinfunction "A_A") (pintype "passive"))
      (node (ref "MINI_USB") (pin "1") (pinfunction "1_1") (pintype "input"))
      (node (ref "P_USB") (pin "A") (pinfunction "A_A") (pintype "passive"))
      (node (ref "U13") (pin "4") (pinfunction "VDD_4") (pintype "bidirectional"))
    )
    (net (code "45") (name "AGND") (class "Default")
      (node (ref "C1") (pin "1") (pinfunction "1_1") (pintype "passive"))
      (node (ref "C2") (pin "1") (pinfunction "1_1") (pintype "passive"))
      (node (ref "C26") (pin "1") (pinfunction "1_1") (pintype "passive"))
      (node (ref "C27") (pin "1") (pinfunction "1_1") (pintype "passive"))
      (node (ref "C3") (pin "1") (pinfunction "1_1") (pintype "passive"))
      (node (ref "C8") (pin "2") (pinfunction "2_2") (pintype "passive"))
      (node (ref "JP2") (pin "10") (pinfunction "10_10") (pintype "passive"))
      (node (ref "JP2") (pin "12") (pinfunction "12_12") (pintype "passive"))
      (node (ref "JP2") (pin "2") (pinfunction "2_2") (pintype "passive"))
      (node (ref "JP2") (pin "4") (pinfunction "4_4") (pintype "passive"))
      (node (ref "JP2") (pin "6") (pinfunction "6_6") (pintype "passive"))
      (node (ref "JP2") (pin "8") (pinfunction "8_8") (pintype "passive"))
      (node (ref "R17") (pin "1") (pinfunction "1_1") (pintype "passive"))
      (node (ref "R19") (pin "1") (pinfunction "1_1") (pintype "passive"))
      (node (ref "R2") (pin "2") (pinfunction "2_2") (pintype "passive"))
      (node (ref "R7") (pin "2") (pinfunction "2_2") (pintype "passive"))
      (node (ref "U1") (pin "41") (pinfunction "AVSS_41") (pintype "bidirectional"))
      (node (ref "U1") (pin "44") (pinfunction "AVSS_44") (pintype "bidirectional"))
      (node (ref "U1") (pin "47") (pinfunction "AVSS_47") (pintype "bidirectional"))
      (node (ref "U11") (pin "1") (pinfunction "REF_1") (pintype "bidirectional"))
      (node (ref "U11") (pin "2") (pinfunction "GND_2") (pintype "bidirectional"))
      (node (ref "U12") (pin "1") (pinfunction "REF_1") (pintype "bidirectional"))
      (node (ref "U12") (pin "2") (pinfunction "GND_2") (pintype "bidirectional"))
      (node (ref "U2") (pin "4") (pinfunction "V-_4") (pintype "power_in"))
    )
    (net (code "46") (name "GND") (class "Default")
      (node (ref "C10") (pin "2") (pinfunction "2_2") (pintype "passive"))
      (node (ref "C11") (pin "2") (pinfunction "2_2") (pintype "passive"))
      (node (ref "C12") (pin "2") (pinfunction "2_2") (pintype "passive"))
      (node (ref "C13") (pin "2") (pinfunction "2_2") (pintype "passive"))
      (node (ref "C14") (pin "2") (pinfunction "2_2") (pintype "passive"))
      (node (ref "C15") (pin "2") (pinfunction "2_2") (pintype "passive"))
      (node (ref "C16") (pin "2") (pinfunction "2_2") (pintype "passive"))
      (node (ref "C17") (pin "2") (pinfunction "2_2") (pintype "passive"))
      (node (ref "C18") (pin "2") (pinfunction "2_2") (pintype "passive"))
      (node (ref "C19") (pin "2") (pinfunction "2_2") (pintype "passive"))
      (node (ref "C20") (pin "2") (pinfunction "2_2") (pintype "passive"))
      (node (ref "C21") (pin "2") (pinfunction "2_2") (pintype "passive"))
      (node (ref "C22") (pin "2") (pinfunction "2_2") (pintype "passive"))
      (node (ref "C23") (pin "2") (pinfunction "2_2") (pintype "passive"))
      (node (ref "C25") (pin "2") (pinfunction "2_2") (pintype "passive"))
      (node (ref "C28") (pin "2") (pinfunction "2_2") (pintype "passive"))
      (node (ref "C29") (pin "2") (pinfunction "2_2") (pintype "passive"))
      (node (ref "C30") (pin "2") (pinfunction "2_2") (pintype "passive"))
      (node (ref "C31") (pin "2") (pinfunction "2_2") (pintype "passive"))
      (node (ref "C32") (pin "2") (pinfunction "2_2") (pintype "passive"))
      (node (ref "C33") (pin "2") (pinfunction "2_2") (pintype "passive"))
      (node (ref "C35") (pin "2") (pinfunction "2_2") (pintype "passive"))
      (node (ref "C37") (pin "2") (pinfunction "2_2") (pintype "passive"))
      (node (ref "C38") (pin "2") (pinfunction "2_2") (pintype "passive"))
      (node (ref "C39") (pin "1") (pinfunction "1_1") (pintype "passive"))
      (node (ref "C4") (pin "-") (pinfunction "-_-") (pintype "passive"))
      (node (ref "C40") (pin "2") (pinfunction "2_2") (pintype "passive"))
      (node (ref "C41") (pin "2") (pinfunction "2_2") (pintype "passive"))
      (node (ref "C42") (pin "1") (pinfunction "1_1") (pintype "passive"))
      (node (ref "C43") (pin "2") (pinfunction "2_2") (pintype "passive"))
      (node (ref "C44") (pin "2") (pinfunction "2_2") (pintype "passive"))
      (node (ref "C45") (pin "2") (pinfunction "2_2") (pintype "passive"))
      (node (ref "C47") (pin "2") (pinfunction "2_2") (pintype "passive"))
      (node (ref "C48") (pin "2") (pinfunction "2_2") (pintype "passive"))
      (node (ref "C49") (pin "1") (pinfunction "1_1") (pintype "passive"))
      (node (ref "C5") (pin "2") (pinfunction "2_2") (pintype "passive"))
      (node (ref "C50") (pin "1") (pinfunction "1_1") (pintype "passive"))
      (node (ref "C51") (pin "1") (pinfunction "1_1") (pintype "passive"))
      (node (ref "C6") (pin "1") (pinfunction "1_1") (pintype "passive"))
      (node (ref "C7") (pin "1") (pinfunction "1_1") (pintype "passive"))
      (node (ref "C9") (pin "2") (pinfunction "2_2") (pintype "passive"))
      (node (ref "J100") (pin "2") (pinfunction "2_2") (pintype "passive"))
      (node (ref "J104") (pin "1") (pinfunction "1_1") (pintype "passive"))
      (node (ref "J105") (pin "1") (pinfunction "1_1") (pintype "passive"))
      (node (ref "J106") (pin "1") (pinfunction "1_1") (pintype "passive"))
      (node (ref "J107") (pin "1") (pinfunction "1_1") (pintype "passive"))
      (node (ref "J108") (pin "1") (pinfunction "1_1") (pintype "passive"))
      (node (ref "J109") (pin "1") (pinfunction "1_1") (pintype "passive"))
      (node (ref "J110") (pin "1") (pinfunction "1_1") (pintype "passive"))
      (node (ref "J111") (pin "1") (pinfunction "1_1") (pintype "passive"))
      (node (ref "JP3") (pin "1") (pinfunction "1_1") (pintype "passive"))
      (node (ref "JP3") (pin "11") (pinfunction "11_11") (pintype "passive"))
      (node (ref "JP3") (pin "13") (pinfunction "13_13") (pintype "passive"))
      (node (ref "JP3") (pin "15") (pinfunction "15_15") (pintype "passive"))
      (node (ref "JP3") (pin "3") (pinfunction "3_3") (pintype "passive"))
      (node (ref "JP3") (pin "5") (pinfunction "5_5") (pintype "passive"))
      (node (ref "JP3") (pin "7") (pinfunction "7_7") (pintype "passive"))
      (node (ref "JP3") (pin "9") (pinfunction "9_9") (pintype "passive"))
      (node (ref "JP5") (pin "1") (pinfunction "1_1") (pintype "passive"))
      (node (ref "JP6") (pin "1") (pinfunction "1_1") (pintype "passive"))
      (node (ref "MINI_USB") (pin "5") (pinfunction "5_5") (pintype "input"))
      (node (ref "Q1") (pin "2") (pinfunction "S_2") (pintype "passive"))
      (node (ref "Q3") (pin "1") (pinfunction "S_2_1") (pintype "passive"))
      (node (ref "Q3") (pin "2") (pinfunction "S_3_2") (pintype "passive"))
      (node (ref "Q3") (pin "3") (pinfunction "S_3") (pintype "passive"))
      (node (ref "Q4") (pin "1") (pinfunction "S_2_1") (pintype "passive"))
      (node (ref "Q4") (pin "2") (pinfunction "S_3_2") (pintype "passive"))
      (node (ref "Q4") (pin "3") (pinfunction "S_3") (pintype "passive"))
      (node (ref "Q5") (pin "1") (pinfunction "S_2_1") (pintype "passive"))
      (node (ref "Q5") (pin "2") (pinfunction "S_3_2") (pintype "passive"))
      (node (ref "Q5") (pin "3") (pinfunction "S_3") (pintype "passive"))
      (node (ref "Q7") (pin "1") (pinfunction "S_2_1") (pintype "passive"))
      (node (ref "Q7") (pin "2") (pinfunction "S_3_2") (pintype "passive"))
      (node (ref "Q7") (pin "3") (pinfunction "S_3") (pintype "passive"))
      (node (ref "R21") (pin "1") (pinfunction "1_1") (pintype "passive"))
      (node (ref "R23") (pin "1") (pinfunction "1_1") (pintype "passive"))
      (node (ref "R25") (pin "1") (pinfunction "1_1") (pintype "passive"))
      (node (ref "R27") (pin "1") (pinfunction "1_1") (pintype "passive"))
      (node (ref "R29") (pin "1") (pinfunction "1_1") (pintype "passive"))
      (node (ref "R35") (pin "1") (pinfunction "1_1") (pintype "passive"))
      (node (ref "R36") (pin "1") (pinfunction "1_1") (pintype "passive"))
      (node (ref "R37") (pin "1") (pinfunction "1_1") (pintype "passive"))
      (node (ref "R41") (pin "2") (pinfunction "2_2") (pintype "passive"))
      (node (ref "R42") (pin "2") (pinfunction "2_2") (pintype "passive"))
      (node (ref "R47") (pin "2") (pinfunction "2_2") (pintype "passive"))
      (node (ref "R51") (pin "2") (pinfunction "2_2") (pintype "passive"))
      (node (ref "R53") (pin "2") (pinfunction "2_2") (pintype "passive"))
      (node (ref "R55") (pin "2") (pinfunction "2_2") (pintype "passive"))
      (node (ref "R56") (pin "1") (pinfunction "1_1") (pintype "passive"))
      (node (ref "R58") (pin "1") (pinfunction "1_1") (pintype "passive"))
      (node (ref "R60") (pin "1") (pinfunction "1_1") (pintype "passive"))
      (node (ref "R62") (pin "2") (pinfunction "2_2") (pintype "passive"))
      (node (ref "RT4") (pin "2") (pinfunction "2_2") (pintype "passive"))
      (node (ref "RTH") (pin "1") (pinfunction "1_1") (pintype "passive"))
      (node (ref "U1") (pin "36") (pinfunction "DVSS_36") (pintype "bidirectional"))
      (node (ref "U1") (pin "VSS_QFN") (pinfunction "VSS_QFN_VSS_QFN") (pintype "bidirectional"))
      (node (ref "U10") (pin "11") (pinfunction "GND_11") (pintype "power_in"))
      (node (ref "U10") (pin "17") (pinfunction "EPAD_17") (pintype "power_in"))
      (node (ref "U10") (pin "7") (pinfunction "TERM_EN_7") (pintype "input"))
      (node (ref "U10") (pin "V") (pinfunction "EPAD_V") (pintype "power_in"))
      (node (ref "U10") (pin "V_1") (pinfunction "EPAD_V_1") (pintype "power_in"))
      (node (ref "U10") (pin "V_2") (pinfunction "EPAD_V_2") (pintype "power_in"))
      (node (ref "U10") (pin "V_3") (pinfunction "EPAD_V_3") (pintype "power_in"))
      (node (ref "U13") (pin "2") (pinfunction "VSS_2") (pintype "bidirectional"))
      (node (ref "U14") (pin "P$2") (pinfunction "GND_P$2") (pintype "bidirectional"))
      (node (ref "U14") (pin "P2") (pinfunction "GND_P2") (pintype "bidirectional"))
      (node (ref "U15") (pin "P$20") (pinfunction "AGND_P$20") (pintype "bidirectional"))
      (node (ref "U15") (pin "PGND1") (pinfunction "PGND_PGND1") (pintype "bidirectional"))
      (node (ref "U15") (pin "PGND10") (pinfunction "PGND_PGND10") (pintype "bidirectional"))
      (node (ref "U15") (pin "PGND11") (pinfunction "PGND_PGND11") (pintype "bidirectional"))
      (node (ref "U15") (pin "PGND12") (pinfunction "PGND_PGND12") (pintype "bidirectional"))
      (node (ref "U15") (pin "PGND2") (pinfunction "PGND_PGND2") (pintype "bidirectional"))
      (node (ref "U15") (pin "PGND3") (pinfunction "PGND_PGND3") (pintype "bidirectional"))
      (node (ref "U15") (pin "PGND4") (pinfunction "PGND_PGND4") (pintype "bidirectional"))
      (node (ref "U15") (pin "PGND5") (pinfunction "PGND_PGND5") (pintype "bidirectional"))
      (node (ref "U15") (pin "PGND6") (pinfunction "PGND_PGND6") (pintype "bidirectional"))
      (node (ref "U15") (pin "PGND7") (pinfunction "PGND_PGND7") (pintype "bidirectional"))
      (node (ref "U15") (pin "PGND8") (pinfunction "PGND_PGND8") (pintype "bidirectional"))
      (node (ref "U15") (pin "PGND9") (pinfunction "PGND_PGND9") (pintype "bidirectional"))
      (node (ref "U3") (pin "1") (pinfunction "GND_1") (pintype "bidirectional"))
      (node (ref "U4") (pin "10") (pinfunction "PFM_PWM_10") (pintype "input"))
      (node (ref "U4") (pin "2") (pinfunction "PGND_2") (pintype "power_in"))
      (node (ref "U4") (pin "9") (pinfunction "GND_9") (pintype "power_in"))
      (node (ref "U5") (pin "10") (pinfunction "PFM_PWM_10") (pintype "input"))
      (node (ref "U5") (pin "2") (pinfunction "PGND_2") (pintype "power_in"))
      (node (ref "U5") (pin "9") (pinfunction "GND_9") (pintype "power_in"))
      (node (ref "U6") (pin "10") (pinfunction "PFM_PWM_10") (pintype "input"))
      (node (ref "U6") (pin "2") (pinfunction "PGND_2") (pintype "power_in"))
      (node (ref "U6") (pin "9") (pinfunction "GND_9") (pintype "power_in"))
      (node (ref "U7") (pin "EXPAD") (pinfunction "GND_EXPAD") (pintype "power_in"))
      (node (ref "U7") (pin "GND1") (pinfunction "GND1_GND1") (pintype "power_in"))
      (node (ref "U7") (pin "GND2") (pinfunction "GND2_GND2") (pintype "power_in"))
      (node (ref "U7") (pin "GND3") (pinfunction "GND3_GND3") (pintype "power_in"))
      (node (ref "U7") (pin "GND4") (pinfunction "GND4_GND4") (pintype "power_in"))
      (node (ref "U7") (pin "GND5") (pinfunction "GND5_GND5") (pintype "power_in"))
      (node (ref "U8") (pin "EXPAD") (pinfunction "GND_EXPAD") (pintype "power_in"))
      (node (ref "U8") (pin "GND1") (pinfunction "GND1_GND1") (pintype "power_in"))
      (node (ref "U8") (pin "GND2") (pinfunction "GND2_GND2") (pintype "power_in"))
      (node (ref "U8") (pin "GND3") (pinfunction "GND3_GND3") (pintype "power_in"))
      (node (ref "U8") (pin "GND4") (pinfunction "GND4_GND4") (pintype "power_in"))
      (node (ref "U8") (pin "GND5") (pinfunction "GND5_GND5") (pintype "power_in"))
      (node (ref "U9") (pin "1") (pinfunction "GND_1") (pintype "bidirectional"))
      (node (ref "X1") (pin "P3") (pinfunction "GND_P3") (pintype "power_in"))
    )
    (net (code "47") (name "Net-(+3V3_1-PadC)") (class "Default")
      (node (ref "+3V3_1") (pin "C") (pinfunction "C_C") (pintype "passive"))
      (node (ref "R11") (pin "2") (pinfunction "2_2") (pintype "passive"))
    )
    (net (code "48") (name "Net-(+3V3_2-PadC)") (class "Default")
      (node (ref "+3V3_2") (pin "C") (pinfunction "C_C") (pintype "passive"))
      (node (ref "R12") (pin "2") (pinfunction "2_2") (pintype "passive"))
    )
    (net (code "49") (name "Net-(+3V3_M-PadC)") (class "Default")
      (node (ref "+3V3_M") (pin "C") (pinfunction "C_C") (pintype "passive"))
      (node (ref "R10") (pin "2") (pinfunction "2_2") (pintype "passive"))
    )
    (net (code "50") (name "Net-(+5V1-PadC)") (class "Default")
      (node (ref "+5V1") (pin "C") (pinfunction "C_C") (pintype "passive"))
      (node (ref "R13") (pin "2") (pinfunction "2_2") (pintype "passive"))
    )
    (net (code "51") (name "Net-(+5V2-PadC)") (class "Default")
      (node (ref "+5V2") (pin "C") (pinfunction "C_C") (pintype "passive"))
      (node (ref "R14") (pin "2") (pinfunction "2_2") (pintype "passive"))
    )
    (net (code "52") (name "Net-(+11V-PadC)") (class "Default")
      (node (ref "+11V") (pin "C") (pinfunction "C_C") (pintype "passive"))
      (node (ref "R15") (pin "2") (pinfunction "2_2") (pintype "passive"))
    )
    (net (code "53") (name "Net-(C33-Pad1)") (class "Default")
      (node (ref "C33") (pin "1") (pinfunction "1_1") (pintype "passive"))
      (node (ref "R44") (pin "1") (pinfunction "1_1") (pintype "passive"))
    )
    (net (code "54") (name "Net-(C41-Pad1)") (class "Default")
      (node (ref "C41") (pin "1") (pinfunction "1_1") (pintype "passive"))
      (node (ref "R59") (pin "1") (pinfunction "1_1") (pintype "passive"))
    )
    (net (code "55") (name "Net-(C_USB-PadC)") (class "Default")
      (node (ref "C_USB") (pin "C") (pinfunction "C_C") (pintype "passive"))
      (node (ref "R48") (pin "1") (pinfunction "1_1") (pintype "passive"))
    )
    (net (code "56") (name "Net-(D1-A1)") (class "Default")
      (node (ref "C23") (pin "1") (pinfunction "1_1") (pintype "passive"))
      (node (ref "D1") (pin "1") (pinfunction "A1_1") (pintype "passive"))
      (node (ref "D1") (pin "2") (pinfunction "A2_2") (pintype "passive"))
      (node (ref "U10") (pin "12") (pinfunction "REGN_12") (pintype "power_in"))
    )
    (net (code "57") (name "Net-(D1-CC)") (class "Default")
      (node (ref "C34") (pin "2") (pinfunction "2_2") (pintype "passive"))
      (node (ref "D1") (pin "3") (pinfunction "CC_3") (pintype "passive"))
      (node (ref "U10") (pin "16") (pinfunction "BTST_16") (pintype "power_in"))
    )
    (net (code "58") (name "Net-(DIRECT-PadC)") (class "Default")
      (node (ref "DIRECT") (pin "C") (pinfunction "C_C") (pintype "passive"))
      (node (ref "R16") (pin "2") (pinfunction "2_2") (pintype "passive"))
    )
    (net (code "59") (name "Net-(J100-Pad1)") (class "Default")
      (node (ref "J100") (pin "1") (pinfunction "1_1") (pintype "passive"))
      (node (ref "R49") (pin "2") (pinfunction "2_2") (pintype "passive"))
    )
    (net (code "60") (name "Net-(J101-Pad2)") (class "Default")
      (node (ref "J101") (pin "2") (pinfunction "2_2") (pintype "passive"))
      (node (ref "R48") (pin "2") (pinfunction "2_2") (pintype "passive"))
    )
    (net (code "61") (name "Net-(J102-Pad2)") (class "Default")
      (node (ref "J102") (pin "2") (pinfunction "2_2") (pintype "passive"))
      (node (ref "STAT2") (pin "C") (pinfunction "C_C") (pintype "passive"))
    )
    (net (code "62") (name "Net-(J103-Pad2)") (class "Default")
      (node (ref "J103") (pin "2") (pinfunction "2_2") (pintype "passive"))
      (node (ref "STAT1") (pin "C") (pinfunction "C_C") (pintype "passive"))
    )
    (net (code "63") (name "Net-(J104-Pad2)") (class "Default")
      (node (ref "J104") (pin "2") (pinfunction "2_2") (pintype "passive"))
      (node (ref "R16") (pin "1") (pinfunction "1_1") (pintype "passive"))
    )
    (net (code "64") (name "Net-(J105-Pad2)") (class "Default")
      (node (ref "J105") (pin "2") (pinfunction "2_2") (pintype "passive"))
      (node (ref "R15") (pin "1") (pinfunction "1_1") (pintype "passive"))
    )
    (net (code "65") (name "Net-(J106-Pad2)") (class "Default")
      (node (ref "J106") (pin "2") (pinfunction "2_2") (pintype "passive"))
      (node (ref "R14") (pin "1") (pinfunction "1_1") (pintype "passive"))
    )
    (net (code "66") (name "Net-(J107-Pad2)") (class "Default")
      (node (ref "J107") (pin "2") (pinfunction "2_2") (pintype "passive"))
      (node (ref "R13") (pin "1") (pinfunction "1_1") (pintype "passive"))
    )
    (net (code "67") (name "Net-(J108-Pad2)") (class "Default")
      (node (ref "J108") (pin "2") (pinfunction "2_2") (pintype "passive"))
      (node (ref "R12") (pin "1") (pinfunction "1_1") (pintype "passive"))
    )
    (net (code "68") (name "Net-(J109-Pad2)") (class "Default")
      (node (ref "J109") (pin "2") (pinfunction "2_2") (pintype "passive"))
      (node (ref "R11") (pin "1") (pinfunction "1_1") (pintype "passive"))
    )
    (net (code "69") (name "Net-(J110-Pad2)") (class "Default")
      (node (ref "J110") (pin "2") (pinfunction "2_2") (pintype "passive"))
      (node (ref "R10") (pin "1") (pinfunction "1_1") (pintype "passive"))
    )
    (net (code "70") (name "Net-(J111-Pad2)") (class "Default")
      (node (ref "J111") (pin "2") (pinfunction "2_2") (pintype "passive"))
      (node (ref "R9") (pin "1") (pinfunction "1_1") (pintype "passive"))
    )
    (net (code "71") (name "Net-(L1-1)") (class "Default")
      (node (ref "L1") (pin "P$1") (pinfunction "1_P$1") (pintype "passive"))
      (node (ref "U4") (pin "3") (pinfunction "L1_3") (pintype "passive"))
    )
    (net (code "72") (name "Net-(L1-2)") (class "Default")
      (node (ref "L1") (pin "P$2") (pinfunction "2_P$2") (pintype "passive"))
      (node (ref "U4") (pin "1") (pinfunction "L2_1") (pintype "passive"))
    )
    (net (code "73") (name "Net-(L2-1)") (class "Default")
      (node (ref "L2") (pin "P$1") (pinfunction "1_P$1") (pintype "passive"))
      (node (ref "U5") (pin "3") (pinfunction "L1_3") (pintype "passive"))
    )
    (net (code "74") (name "Net-(L2-2)") (class "Default")
      (node (ref "L2") (pin "P$2") (pinfunction "2_P$2") (pintype "passive"))
      (node (ref "U5") (pin "1") (pinfunction "L2_1") (pintype "passive"))
    )
    (net (code "75") (name "Net-(L3-1)") (class "Default")
      (node (ref "L3") (pin "P$1") (pinfunction "1_P$1") (pintype "passive"))
      (node (ref "U6") (pin "3") (pinfunction "L1_3") (pintype "passive"))
    )
    (net (code "76") (name "Net-(L3-2)") (class "Default")
      (node (ref "L3") (pin "P$2") (pinfunction "2_P$2") (pintype "passive"))
      (node (ref "U6") (pin "1") (pinfunction "L2_1") (pintype "passive"))
    )
    (net (code "77") (name "Net-(L4-2)") (class "Default")
      (node (ref "L4") (pin "P$2") (pinfunction "2_P$2") (pintype "passive"))
      (node (ref "U7") (pin "1") (pinfunction "SW_1") (pintype "power_in"))
      (node (ref "U7") (pin "2") (pinfunction "SW_2") (pintype "power_in"))
    )
    (net (code "78") (name "Net-(L5-2)") (class "Default")
      (node (ref "L5") (pin "P$2") (pinfunction "2_P$2") (pintype "passive"))
      (node (ref "U8") (pin "1") (pinfunction "SW_1") (pintype "power_in"))
      (node (ref "U8") (pin "2") (pinfunction "SW_2") (pintype "power_in"))
    )
    (net (code "79") (name "Net-(L6-Pad2)") (class "Default")
      (node (ref "L6") (pin "2") (pinfunction "2_2") (pintype "passive"))
      (node (ref "RS2") (pin "I1") (pinfunction "I1_I1") (pintype "bidirectional"))
    )
    (net (code "80") (name "Net-(L7-1)") (class "Default")
      (node (ref "C44") (pin "1") (pinfunction "1_1") (pintype "passive"))
      (node (ref "C45") (pin "1") (pinfunction "1_1") (pintype "passive"))
      (node (ref "C47") (pin "1") (pinfunction "1_1") (pintype "passive"))
      (node (ref "L7") (pin "P$1") (pinfunction "1_P$1") (pintype "passive"))
      (node (ref "Q6") (pin "1") (pinfunction "S_1") (pintype "passive"))
      (node (ref "Q6") (pin "2") (pinfunction "S_2") (pintype "passive"))
      (node (ref "Q6") (pin "3") (pinfunction "S_3") (pintype "passive"))
      (node (ref "U15") (pin "P$2") (pinfunction "EN_P$2") (pintype "bidirectional"))
      (node (ref "U15") (pin "P$9") (pinfunction "VIN_P$9") (pintype "bidirectional"))
    )
    (net (code "81") (name "Net-(L7-2)") (class "Default")
      (node (ref "C46") (pin "1") (pinfunction "1_1") (pintype "passive"))
      (node (ref "L7") (pin "P$2") (pinfunction "2_P$2") (pintype "passive"))
      (node (ref "R57") (pin "2") (pinfunction "2_2") (pintype "passive"))
      (node (ref "U15") (pin "P$4") (pinfunction "SW1_P$4") (pintype "bidirectional"))
      (node (ref "U15") (pin "P$5") (pinfunction "SW2_P$5") (pintype "bidirectional"))
      (node (ref "U15") (pin "P$6") (pinfunction "SW3_P$6") (pintype "bidirectional"))
      (node (ref "U15") (pin "P$7") (pinfunction "SW4_P$7") (pintype "bidirectional"))
    )
    (net (code "82") (name "Net-(P_USB-PadC)") (class "Default")
      (node (ref "P_USB") (pin "C") (pinfunction "C_C") (pintype "passive"))
      (node (ref "R49") (pin "1") (pinfunction "1_1") (pintype "passive"))
    )
    (net (code "83") (name "Net-(Q1-D)") (class "Default")
      (node (ref "Q1") (pin "3") (pinfunction "D_3") (pintype "passive"))
      (node (ref "R32") (pin "1") (pinfunction "1_1") (pintype "passive"))
      (node (ref "R36") (pin "2") (pinfunction "2_2") (pintype "passive"))
      (node (ref "U10") (pin "2") (pinfunction "MPPSET_2") (pintype "input"))
    )
    (net (code "84") (name "Net-(Q2-G)") (class "Default")
      (node (ref "Q2") (pin "4") (pinfunction "G_4") (pintype "passive"))
      (node (ref "U10") (pin "15") (pinfunction "HIDRV_15") (pintype "output"))
    )
    (net (code "85") (name "Net-(Q2-S)") (class "Default")
      (node (ref "C34") (pin "1") (pinfunction "1_1") (pintype "passive"))
      (node (ref "L6") (pin "1") (pinfunction "1_1") (pintype "passive"))
      (node (ref "Q2") (pin "1") (pinfunction "S_2_1") (pintype "passive"))
      (node (ref "Q2") (pin "2") (pinfunction "S_3_2") (pintype "passive"))
      (node (ref "Q2") (pin "3") (pinfunction "S_3") (pintype "passive"))
      (node (ref "Q7") (pin "5") (pinfunction "D_2_5") (pintype "passive"))
      (node (ref "Q7") (pin "6") (pinfunction "D_3_6") (pintype "passive"))
      (node (ref "Q7") (pin "7") (pinfunction "D_4_7") (pintype "passive"))
      (node (ref "Q7") (pin "8") (pinfunction "D_8") (pintype "passive"))
      (node (ref "U10") (pin "14") (pinfunction "PH_14") (pintype "power_in"))
    )
    (net (code "86") (name "Net-(Q3-G)") (class "Default")
      (node (ref "Q3") (pin "4") (pinfunction "G_4") (pintype "passive"))
      (node (ref "R50") (pin "1") (pinfunction "1_1") (pintype "passive"))
    )
    (net (code "87") (name "Net-(Q4-G)") (class "Default")
      (node (ref "Q4") (pin "4") (pinfunction "G_4") (pintype "passive"))
      (node (ref "R52") (pin "1") (pinfunction "1_1") (pintype "passive"))
    )
    (net (code "88") (name "Net-(Q5-G)") (class "Default")
      (node (ref "Q5") (pin "4") (pinfunction "G_4") (pintype "passive"))
      (node (ref "R54") (pin "1") (pinfunction "1_1") (pintype "passive"))
    )
    (net (code "89") (name "Net-(Q6A-G)") (class "Default")
      (node (ref "Q6") (pin "4") (pinfunction "G_4") (pintype "passive"))
      (node (ref "U14") (pin "P$4") (pinfunction "OUT_P$4") (pintype "bidirectional"))
      (node (ref "U14") (pin "P4") (pinfunction "OUT_P4") (pintype "bidirectional"))
    )
    (net (code "90") (name "Net-(Q7-G)") (class "Default")
      (node (ref "Q7") (pin "4") (pinfunction "G_4") (pintype "passive"))
      (node (ref "U10") (pin "13") (pinfunction "LODRV_13") (pintype "output"))
    )
    (net (code "91") (name "Net-(R9-Pad2)") (class "Default")
      (node (ref "R9") (pin "2") (pinfunction "2_2") (pintype "passive"))
      (node (ref "VCC") (pin "C") (pinfunction "C_C") (pintype "passive"))
    )
    (net (code "92") (name "Net-(R33-Pad1)") (class "Default")
      (node (ref "R33") (pin "1") (pinfunction "1_1") (pintype "passive"))
      (node (ref "STAT1") (pin "A") (pinfunction "A_A") (pintype "passive"))
    )
    (net (code "93") (name "Net-(R34-Pad1)") (class "Default")
      (node (ref "R34") (pin "1") (pinfunction "1_1") (pintype "passive"))
      (node (ref "STAT2") (pin "A") (pinfunction "A_A") (pintype "passive"))
    )
    (net (code "94") (name "Net-(U1-LFXIN)") (class "Default")
      (node (ref "C6") (pin "2") (pinfunction "2_2") (pintype "passive"))
      (node (ref "U1") (pin "45") (pinfunction "LFXIN_45") (pintype "bidirectional"))
      (node (ref "X1") (pin "P2") (pinfunction "2_P2") (pintype "bidirectional"))
    )
    (net (code "95") (name "Net-(U1-LFXOUT)") (class "Default")
      (node (ref "C7") (pin "2") (pinfunction "2_2") (pintype "passive"))
      (node (ref "U1") (pin "46") (pinfunction "LFXOUT_46") (pintype "bidirectional"))
      (node (ref "X1") (pin "P1") (pinfunction "1_P1") (pintype "bidirectional"))
    )
    (net (code "96") (name "Net-(U1-P2.0{slash}TB0.6{slash}UCA0TXD{slash}UCA0SIMO)") (class "Default")
      (node (ref "DIGITAL") (pin "4") (pinfunction "4_4") (pintype "passive"))
      (node (ref "U1") (pin "24") (pinfunction "P2.0/TB0.6/UCA0TXD/UCA0SIMO_24") (pintype "bidirectional"))
    )
    (net (code "97") (name "Net-(U1-P2.1{slash}TB0.0{slash}UCA0RXD{slash}UCA0SOMI)") (class "Default")
      (node (ref "DIGITAL") (pin "3") (pinfunction "3_3") (pintype "passive"))
      (node (ref "U1") (pin "25") (pinfunction "P2.1/TB0.0/UCA0RXD/UCA0SOMI_25") (pintype "bidirectional"))
    )
    (net (code "98") (name "Net-(U1-P2.3{slash}TA0.0{slash}UCA1STE{slash}A6)") (class "Default")
      (node (ref "DIGITAL") (pin "2") (pinfunction "2_2") (pintype "passive"))
      (node (ref "U1") (pin "39") (pinfunction "P2.3/TA0.0/UCA1STE/A6_39") (pintype "bidirectional"))
    )
    (net (code "99") (name "Net-(U1-P2.4{slash}TA1.0{slash}UCA1CLK{slash}A7)") (class "Default")
      (node (ref "DIGITAL") (pin "1") (pinfunction "1_1") (pintype "passive"))
      (node (ref "U1") (pin "40") (pinfunction "P2.4/TA1.0/UCA1CLK/A7_40") (pintype "bidirectional"))
    )
    (net (code "100") (name "Net-(U1-P2.5{slash}TB0.0{slash}UCA1TXD{slash}UCA1SIMO)") (class "Default")
      (node (ref "DIGITAL") (pin "6") (pinfunction "6_6") (pintype "passive"))
      (node (ref "U1") (pin "20") (pinfunction "P2.5/TB0.0/UCA1TXD/UCA1SIMO_20") (pintype "bidirectional"))
    )
    (net (code "101") (name "Net-(U1-P2.6{slash}TB0.1{slash}UCA1RXD{slash}UCA1SOMI)") (class "Default")
      (node (ref "DIGITAL") (pin "5") (pinfunction "5_5") (pintype "passive"))
      (node (ref "U1") (pin "21") (pinfunction "P2.6/TB0.1/UCA1RXD/UCA1SOMI_21") (pintype "bidirectional"))
    )
    (net (code "102") (name "Net-(U1-RST{slash}SBWTDIO)") (class "Default")
      (node (ref "JP1") (pin "1") (pinfunction "1_1") (pintype "passive"))
      (node (ref "R1") (pin "1") (pinfunction "1_1") (pintype "passive"))
      (node (ref "U1") (pin "23") (pinfunction "RST/SBWTDIO_23") (pintype "bidirectional"))
    )
    (net (code "103") (name "Net-(U1-TEST{slash}SBWTCK)") (class "Default")
      (node (ref "JP1") (pin "2") (pinfunction "2_2") (pintype "passive"))
      (node (ref "U1") (pin "22") (pinfunction "TEST/SBWTCK_22") (pintype "bidirectional"))
    )
    (net (code "104") (name "Net-(U2A-+IN)") (class "Default")
      (node (ref "R17") (pin "2") (pinfunction "2_2") (pintype "passive"))
      (node (ref "R18") (pin "1") (pinfunction "1_1") (pintype "passive"))
      (node (ref "U2") (pin "3") (pinfunction "+IN_3") (pintype "input"))
    )
    (net (code "105") (name "Net-(U2A--IN)") (class "Default")
      (node (ref "R2") (pin "1") (pinfunction "1_1") (pintype "passive"))
      (node (ref "R3") (pin "2") (pinfunction "2_2") (pintype "passive"))
      (node (ref "U2") (pin "2") (pinfunction "-IN_2") (pintype "input"))
    )
    (net (code "106") (name "Net-(U2A-OUT)") (class "Default")
      (node (ref "R3") (pin "1") (pinfunction "1_1") (pintype "passive"))
      (node (ref "R4") (pin "2") (pinfunction "2_2") (pintype "passive"))
      (node (ref "U2") (pin "1") (pinfunction "OUT_1") (pintype "output"))
    )
    (net (code "107") (name "Net-(U2B-+IN)") (class "Default")
      (node (ref "R19") (pin "2") (pinfunction "2_2") (pintype "passive"))
      (node (ref "R20") (pin "1") (pinfunction "1_1") (pintype "passive"))
      (node (ref "U2") (pin "5") (pinfunction "+IN_5") (pintype "input"))
    )
    (net (code "108") (name "Net-(U2B--IN)") (class "Default")
      (node (ref "R6") (pin "2") (pinfunction "2_2") (pintype "passive"))
      (node (ref "R7") (pin "1") (pinfunction "1_1") (pintype "passive"))
      (node (ref "U2") (pin "6") (pinfunction "-IN_6") (pintype "input"))
    )
    (net (code "109") (name "Net-(U2B-OUT)") (class "Default")
      (node (ref "R5") (pin "2") (pinfunction "2_2") (pintype "passive"))
      (node (ref "R6") (pin "1") (pinfunction "1_1") (pintype "passive"))
      (node (ref "U2") (pin "7") (pinfunction "OUT_7") (pintype "output"))
    )
    (net (code "110") (name "Net-(U4-FB)") (class "Default")
      (node (ref "R21") (pin "2") (pinfunction "2_2") (pintype "passive"))
      (node (ref "R22") (pin "1") (pinfunction "1_1") (pintype "passive"))
      (node (ref "U4") (pin "11") (pinfunction "FB_11") (pintype "input"))
    )
    (net (code "111") (name "Net-(U5-FB)") (class "Default")
      (node (ref "R23") (pin "2") (pinfunction "2_2") (pintype "passive"))
      (node (ref "R24") (pin "1") (pinfunction "1_1") (pintype "passive"))
      (node (ref "U5") (pin "11") (pinfunction "FB_11") (pintype "input"))
    )
    (net (code "112") (name "Net-(U6-FB)") (class "Default")
      (node (ref "R25") (pin "2") (pinfunction "2_2") (pintype "passive"))
      (node (ref "R26") (pin "1") (pinfunction "1_1") (pintype "passive"))
      (node (ref "U6") (pin "11") (pinfunction "FB_11") (pintype "input"))
    )
    (net (code "113") (name "Net-(U7-PG)") (class "Default")
      (node (ref "R28") (pin "1") (pinfunction "1_1") (pintype "passive"))
      (node (ref "U7") (pin "5") (pinfunction "PG_5") (pintype "output"))
    )
    (net (code "114") (name "Net-(U7-SS)") (class "Default")
      (node (ref "C15") (pin "1") (pinfunction "1_1") (pintype "passive"))
      (node (ref "U7") (pin "6") (pinfunction "SS_6") (pintype "bidirectional"))
    )
    (net (code "115") (name "Net-(U8-PG)") (class "Default")
      (node (ref "R30") (pin "1") (pinfunction "1_1") (pintype "passive"))
      (node (ref "U8") (pin "5") (pinfunction "PG_5") (pintype "output"))
    )
    (net (code "116") (name "Net-(U8-SS)") (class "Default")
      (node (ref "C19") (pin "1") (pinfunction "1_1") (pintype "passive"))
      (node (ref "U8") (pin "6") (pinfunction "SS_6") (pintype "bidirectional"))
    )
    (net (code "117") (name "Net-(U10-STAT1)") (class "Default")
      (node (ref "J102") (pin "1") (pinfunction "1_1") (pintype "passive"))
      (node (ref "U10") (pin "3") (pinfunction "STAT1_3") (pintype "output"))
    )
    (net (code "118") (name "Net-(U10-STAT2)") (class "Default")
      (node (ref "J103") (pin "1") (pinfunction "1_1") (pintype "passive"))
      (node (ref "U10") (pin "5") (pinfunction "STAT2_5") (pintype "output"))
    )
    (net (code "119") (name "Net-(U10-VCC)") (class "Default")
      (node (ref "C35") (pin "1") (pinfunction "1_1") (pintype "passive"))
      (node (ref "R45") (pin "2") (pinfunction "2_2") (pintype "passive"))
      (node (ref "U10") (pin "1") (pinfunction "VCC_1") (pintype "power_in"))
    )
    (net (code "120") (name "Net-(U10-VFB)") (class "Default")
      (node (ref "C36") (pin "2") (pinfunction "2_2") (pintype "passive"))
      (node (ref "R37") (pin "2") (pinfunction "2_2") (pintype "passive"))
      (node (ref "R39") (pin "1") (pinfunction "1_1") (pintype "passive"))
      (node (ref "R46") (pin "1") (pinfunction "1_1") (pintype "passive"))
      (node (ref "U10") (pin "8") (pinfunction "VFB_8") (pintype "input"))
    )
    (net (code "121") (name "Net-(U10-VREF)") (class "Default")
      (node (ref "C25") (pin "1") (pinfunction "1_1") (pintype "passive"))
      (node (ref "RT3") (pin "1") (pinfunction "1_1") (pintype "passive"))
      (node (ref "U10") (pin "6") (pinfunction "VREF_6") (pintype "power_in"))
    )
    (net (code "122") (name "Net-(U11-IN+)") (class "Default")
      (node (ref "RS1") (pin "V1") (pinfunction "V1_V1") (pintype "bidirectional"))
      (node (ref "U11") (pin "4") (pinfunction "IN+_4") (pintype "bidirectional"))
    )
    (net (code "123") (name "Net-(U11-IN-)") (class "Default")
      (node (ref "RS1") (pin "V2") (pinfunction "V2_V2") (pintype "bidirectional"))
      (node (ref "U11") (pin "5") (pinfunction "IN-_5") (pintype "bidirectional"))
    )
    (net (code "124") (name "Net-(U11-OUT)") (class "Default")
      (node (ref "R40") (pin "2") (pinfunction "2_2") (pintype "passive"))
      (node (ref "U11") (pin "6") (pinfunction "OUT_6") (pintype "bidirectional"))
    )
    (net (code "125") (name "Net-(U12-OUT)") (class "Default")
      (node (ref "R38") (pin "2") (pinfunction "2_2") (pintype "passive"))
      (node (ref "U12") (pin "6") (pinfunction "OUT_6") (pintype "bidirectional"))
    )
    (net (code "126") (name "Net-(U13-PROG)") (class "Default")
      (node (ref "R47") (pin "1") (pinfunction "1_1") (pintype "passive"))
      (node (ref "U13") (pin "5") (pinfunction "PROG_5") (pintype "bidirectional"))
    )
    (net (code "127") (name "Net-(U13-STAT)") (class "Default")
      (node (ref "J101") (pin "1") (pinfunction "1_1") (pintype "passive"))
      (node (ref "U13") (pin "1") (pinfunction "STAT_1") (pintype "bidirectional"))
    )
    (net (code "128") (name "Net-(U15-BOOT)") (class "Default")
      (node (ref "C46") (pin "2") (pinfunction "2_2") (pintype "passive"))
      (node (ref "U15") (pin "P$8") (pinfunction "BOOT_P$8") (pintype "bidirectional"))
    )
    (net (code "129") (name "Net-(U15-COMP)") (class "Default")
      (node (ref "C40") (pin "1") (pinfunction "1_1") (pintype "passive"))
      (node (ref "R59") (pin "2") (pinfunction "2_2") (pintype "passive"))
      (node (ref "U15") (pin "P$18") (pinfunction "COMP_P$18") (pintype "bidirectional"))
    )
    (net (code "130") (name "Net-(U15-FB)") (class "Default")
      (node (ref "R60") (pin "2") (pinfunction "2_2") (pintype "passive"))
      (node (ref "R61") (pin "1") (pinfunction "1_1") (pintype "passive"))
      (node (ref "U15") (pin "P$17") (pinfunction "FB_P$17") (pintype "bidirectional"))
    )
    (net (code "131") (name "Net-(U15-FSW)") (class "Default")
      (node (ref "R57") (pin "1") (pinfunction "1_1") (pintype "passive"))
      (node (ref "U15") (pin "P$3") (pinfunction "FSW_P$3") (pintype "bidirectional"))
    )
    (net (code "132") (name "Net-(U15-ILIM)") (class "Default")
      (node (ref "R58") (pin "2") (pinfunction "2_2") (pintype "passive"))
      (node (ref "U15") (pin "P$19") (pinfunction "ILIM_P$19") (pintype "bidirectional"))
    )
    (net (code "133") (name "Net-(U15-MODE)") (class "Default")
      (node (ref "R62") (pin "1") (pinfunction "1_1") (pintype "passive"))
      (node (ref "U15") (pin "P$13") (pinfunction "MODE_P$13") (pintype "bidirectional"))
    )
    (net (code "134") (name "Net-(U15-SS)") (class "Default")
      (node (ref "C48") (pin "1") (pinfunction "1_1") (pintype "passive"))
      (node (ref "U15") (pin "P$10") (pinfunction "SS_P$10") (pintype "bidirectional"))
    )
    (net (code "135") (name "Net-(U15-VCC)") (class "Default")
      (node (ref "C38") (pin "1") (pinfunction "1_1") (pintype "passive"))
      (node (ref "U15") (pin "P$1") (pinfunction "VCC_P$1") (pintype "bidirectional"))
    )
    (net (code "136") (name "unconnected-(MINI_USB-Pad2)") (class "Default")
      (node (ref "MINI_USB") (pin "2") (pinfunction "2_2") (pintype "input"))
    )
    (net (code "137") (name "unconnected-(MINI_USB-Pad3)") (class "Default")
      (node (ref "MINI_USB") (pin "3") (pinfunction "3_3") (pintype "input"))
    )
    (net (code "138") (name "unconnected-(MINI_USB-Pad4)") (class "Default")
      (node (ref "MINI_USB") (pin "4") (pinfunction "4_4") (pintype "input"))
    )
    (net (code "139") (name "unconnected-(U1-HFXIN-Pad42)") (class "Default")
      (node (ref "U1") (pin "42") (pinfunction "HFXIN_42") (pintype "bidirectional"))
    )
    (net (code "140") (name "unconnected-(U1-HFXOUT-Pad43)") (class "Default")
      (node (ref "U1") (pin "43") (pinfunction "HFXOUT_43") (pintype "bidirectional"))
    )
    (net (code "141") (name "unconnected-(U1-P2.2{slash}TB0.2{slash}UCB0CLK-Pad26)") (class "Default")
      (node (ref "U1") (pin "26") (pinfunction "P2.2/TB0.2/UCB0CLK_26") (pintype "bidirectional"))
    )
    (net (code "142") (name "unconnected-(U1-P2.7-Pad38)") (class "Default")
      (node (ref "U1") (pin "38") (pinfunction "P2.7_38") (pintype "bidirectional"))
    )
    (net (code "143") (name "unconnected-(U1-P3.7{slash}TB0.6-Pad30)") (class "Default")
      (node (ref "U1") (pin "30") (pinfunction "P3.7/TB0.6_30") (pintype "bidirectional"))
    )
    (net (code "144") (name "unconnected-(U1-P4.4{slash}TB0.5-Pad33)") (class "Default")
      (node (ref "U1") (pin "33") (pinfunction "P4.4/TB0.5_33") (pintype "bidirectional"))
    )
    (net (code "145") (name "unconnected-(U1-P4.5-Pad34)") (class "Default")
      (node (ref "U1") (pin "34") (pinfunction "P4.5_34") (pintype "bidirectional"))
    )
    (net (code "146") (name "unconnected-(U1-P4.6-Pad35)") (class "Default")
      (node (ref "U1") (pin "35") (pinfunction "P4.6_35") (pintype "bidirectional"))
    )
    (net (code "147") (name "unconnected-(U1-PJ.3{slash}TCK-Pad15)") (class "Default")
      (node (ref "U1") (pin "15") (pinfunction "PJ.3/TCK_15") (pintype "bidirectional"))
    )
    (net (code "148") (name "unconnected-(U3-OC-Pad5)") (class "Default")
      (node (ref "U3") (pin "5") (pinfunction "OC_5") (pintype "bidirectional"))
    )
    (net (code "149") (name "unconnected-(U7-HYS-Pad8)") (class "Default")
      (node (ref "U7") (pin "8") (pinfunction "HYS_8") (pintype "output"))
    )
    (net (code "150") (name "unconnected-(U8-HYS-Pad8)") (class "Default")
      (node (ref "U8") (pin "8") (pinfunction "HYS_8") (pintype "output"))
    )
    (net (code "151") (name "unconnected-(U9-OC-Pad5)") (class "Default")
      (node (ref "U9") (pin "5") (pinfunction "OC_5") (pintype "bidirectional"))
    )
  )
)
